# Pop-Up_5_2.net
KiCad netlist of a schematic drawn in EAGLE
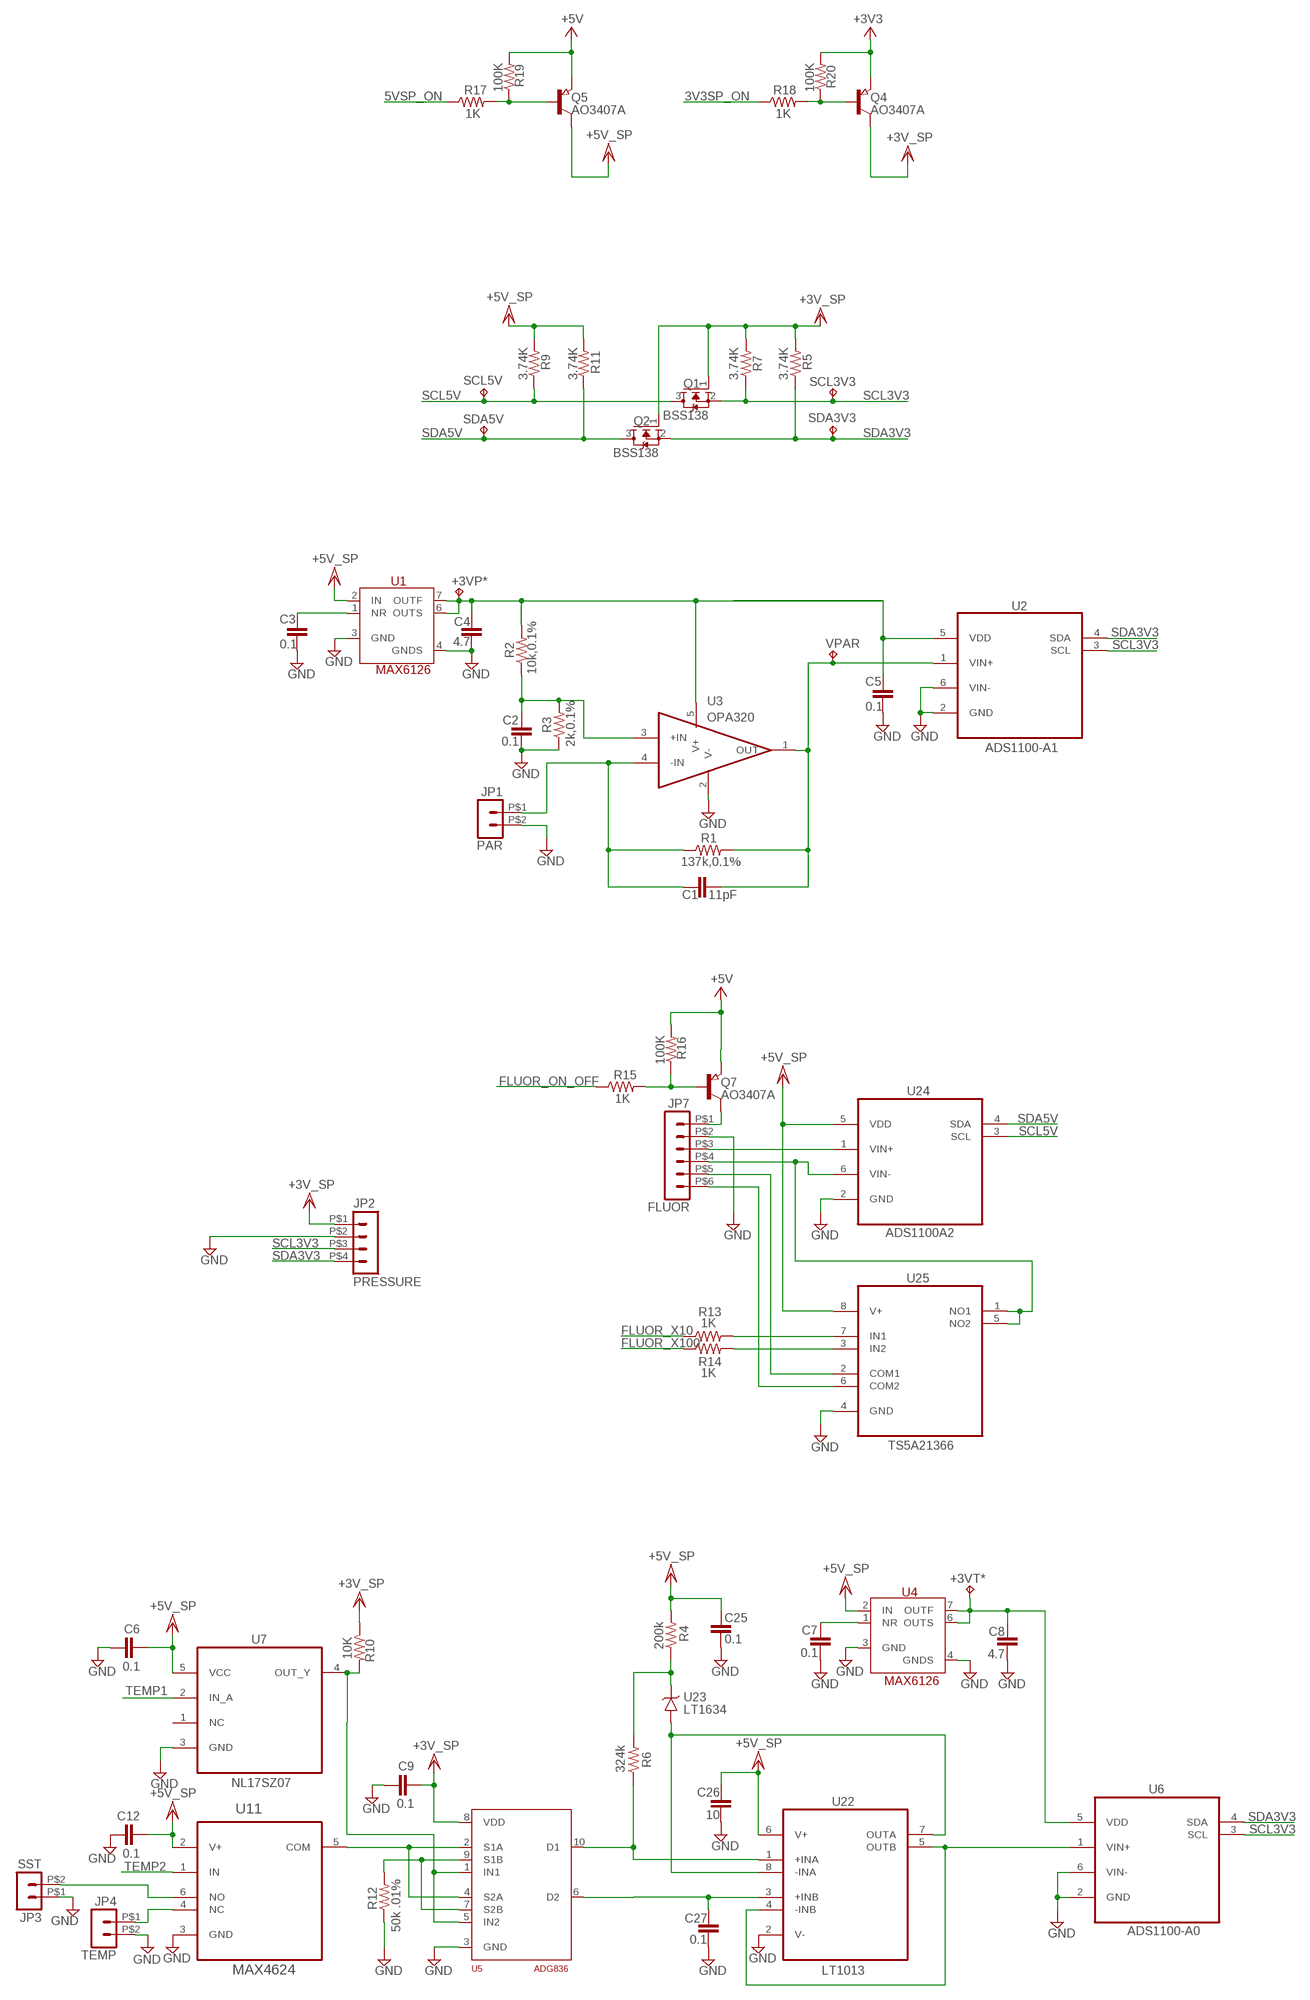
[diagram p0: schematic, sheet 1, part 1 of 2]
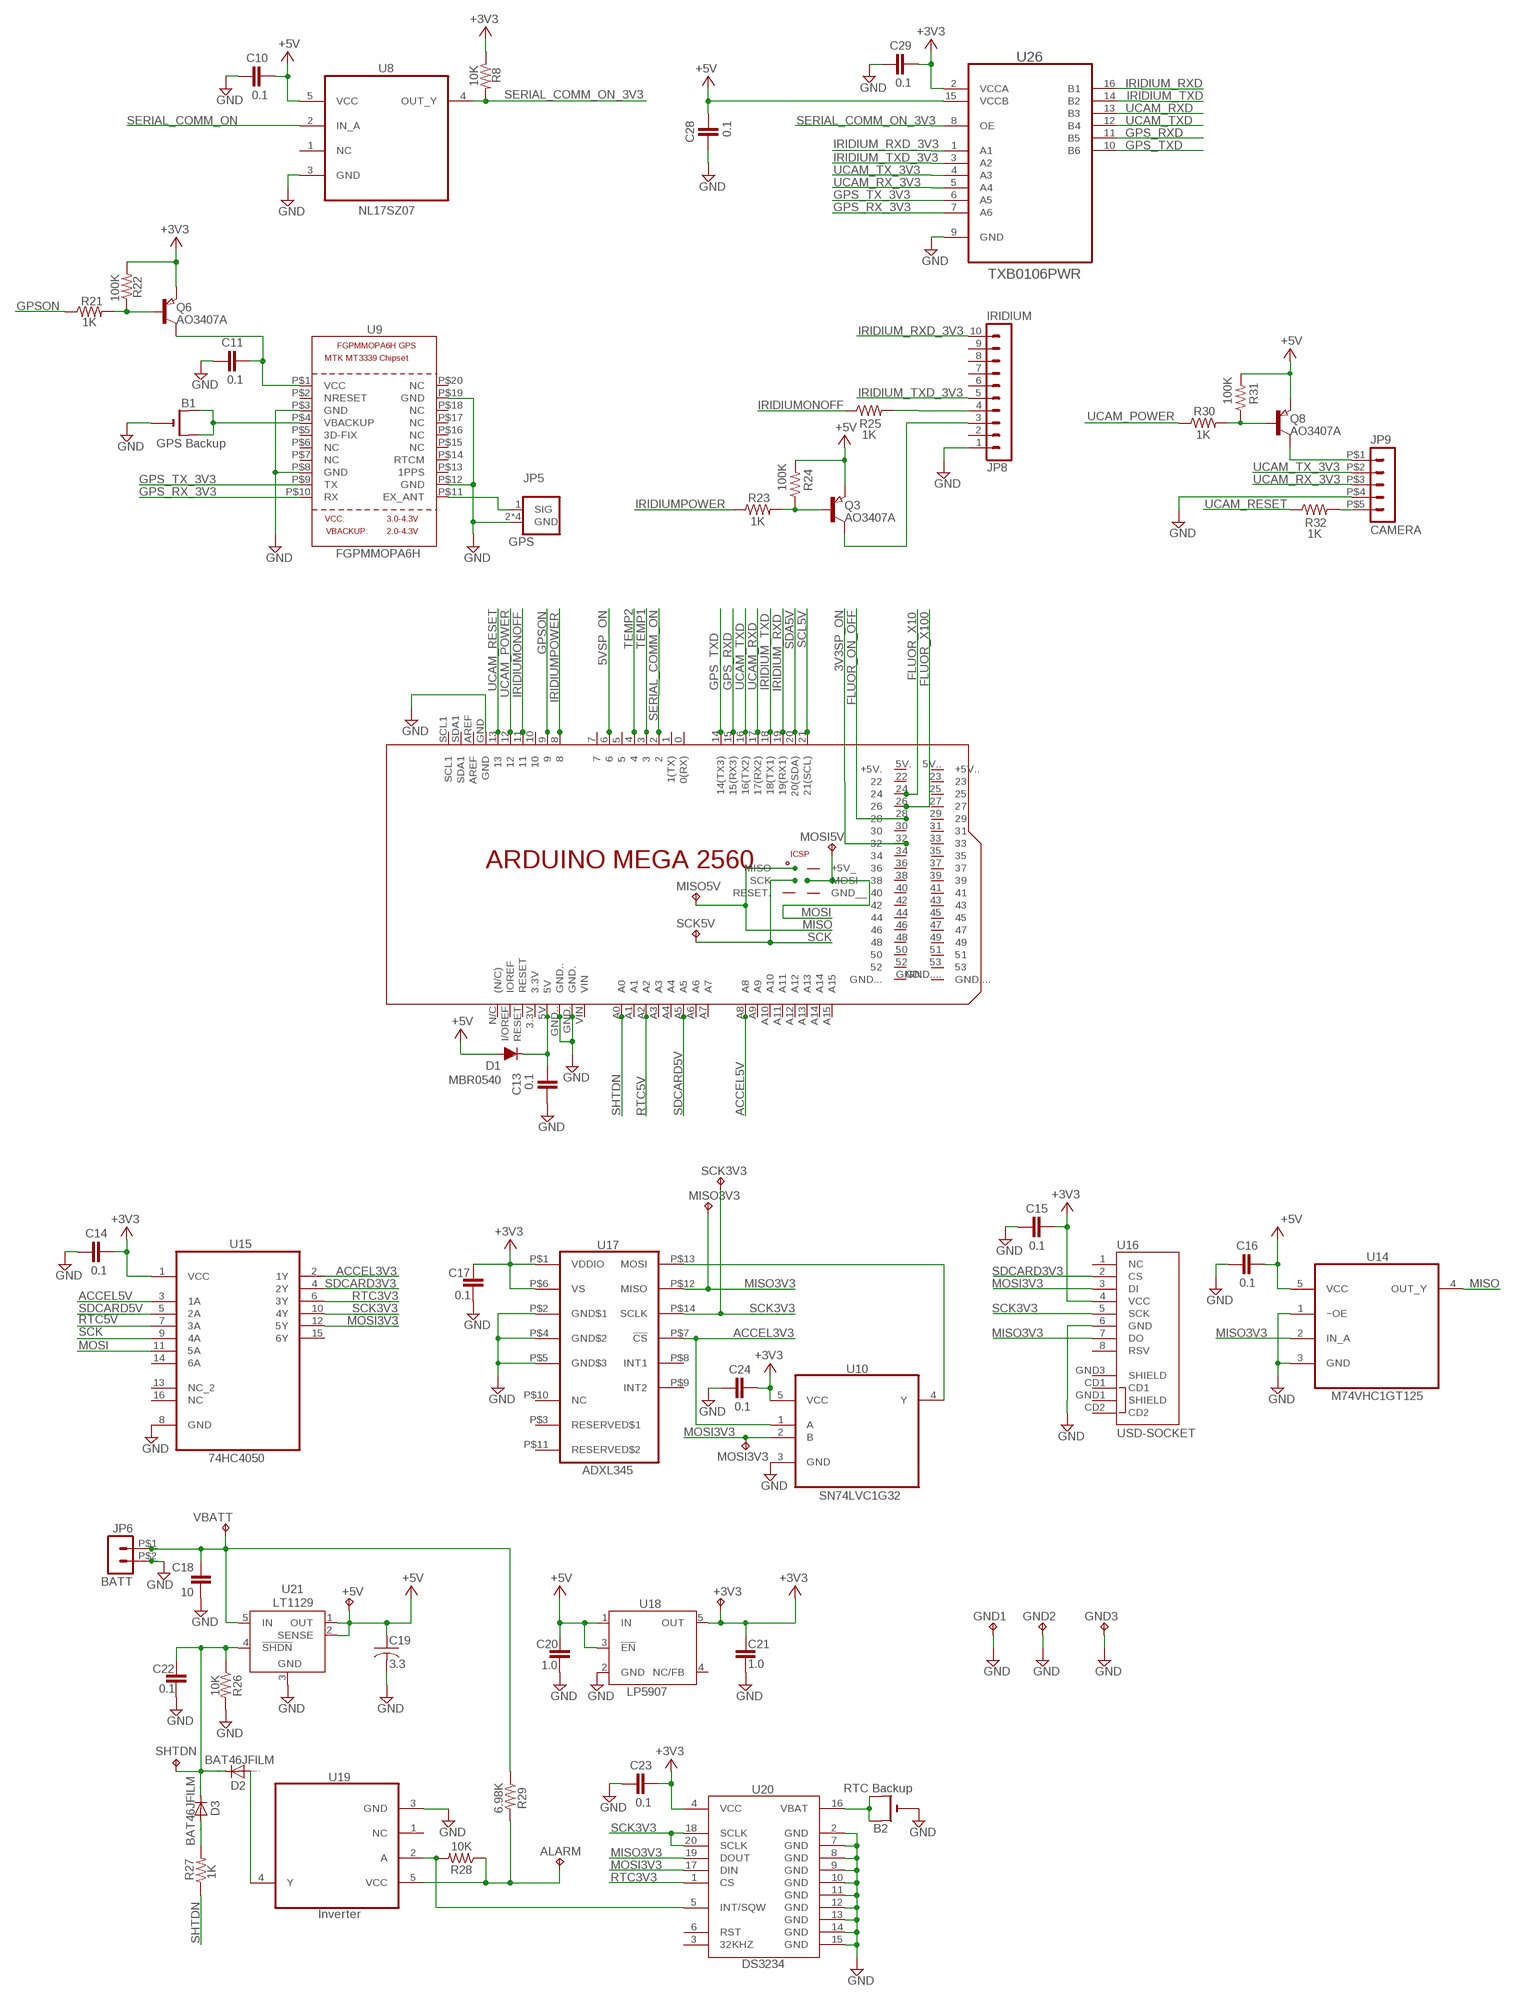
[diagram p1: schematic, sheet 1, part 2 of 2]

(export (version "E")
  (design (tool "Eeschema 10.0.6"))
  (components
    (comp (ref "+3V3")
      (value "TP-040")
      (footprint "eagle-import:TP-040")
      (libsource (lib "eagle-import") (part "TP-040"))
    )
    (comp (ref "+3VP*")
      (value "TP-040")
      (footprint "eagle-import:TP-040")
      (libsource (lib "eagle-import") (part "TP-040"))
    )
    (comp (ref "+3VT*")
      (value "TP-040")
      (footprint "eagle-import:TP-040")
      (libsource (lib "eagle-import") (part "TP-040"))
    )
    (comp (ref "+5V")
      (value "TP-040")
      (footprint "eagle-import:TP-040")
      (libsource (lib "eagle-import") (part "TP-040"))
    )
    (comp (ref "ALARM")
      (value "TP-040")
      (footprint "eagle-import:TP-040")
      (libsource (lib "eagle-import") (part "TP-040"))
    )
    (comp (ref "B1")
      (value "GPS Backup")
      (footprint "eagle-import:CR1220-SMD")
      (libsource (lib "eagle-import") (part "CR1220SMT"))
    )
    (comp (ref "B2")
      (value "RTC Backup")
      (footprint "eagle-import:CR1220-SMD")
      (libsource (lib "eagle-import") (part "CR1220SMT"))
    )
    (comp (ref "C1")
      (value "11pF")
      (footprint "eagle-import:0603-CAP")
      (fields (field (name "MPN") "2222 370 21104"))
      (libsource (lib "eagle-import") (part "CAP0603-CAP"))
    )
    (comp (ref "C2")
      (value "0.1")
      (footprint "eagle-import:0603-CAP")
      (fields (field (name "MPN") "2222 370 21104"))
      (libsource (lib "eagle-import") (part "CAP0603-CAP"))
    )
    (comp (ref "C3")
      (value "0.1")
      (footprint "eagle-import:0603-CAP")
      (fields (field (name "MPN") "2222 370 21104"))
      (libsource (lib "eagle-import") (part "CAP0603-CAP"))
    )
    (comp (ref "C4")
      (value "4.7")
      (footprint "eagle-import:0603-CAP")
      (fields (field (name "MPN") "2222 370 21104"))
      (libsource (lib "eagle-import") (part "CAP0603-CAP"))
    )
    (comp (ref "C5")
      (value "0.1")
      (footprint "eagle-import:0603-CAP")
      (fields (field (name "MPN") "2222 370 21104"))
      (libsource (lib "eagle-import") (part "CAP0603-CAP"))
    )
    (comp (ref "C6")
      (value "0.1")
      (footprint "eagle-import:0603-CAP")
      (fields (field (name "MPN") "2222 370 21104"))
      (libsource (lib "eagle-import") (part "CAP0603-CAP"))
    )
    (comp (ref "C7")
      (value "0.1")
      (footprint "eagle-import:0603-CAP")
      (fields (field (name "MPN") "2222 370 21104"))
      (libsource (lib "eagle-import") (part "CAP0603-CAP"))
    )
    (comp (ref "C8")
      (value "4.7")
      (footprint "eagle-import:0603-CAP")
      (fields (field (name "MPN") "2222 370 21104"))
      (libsource (lib "eagle-import") (part "CAP0603-CAP"))
    )
    (comp (ref "C9")
      (value "0.1")
      (footprint "eagle-import:0603-CAP")
      (fields (field (name "MPN") "2222 370 21104"))
      (libsource (lib "eagle-import") (part "CAP0603-CAP"))
    )
    (comp (ref "C10")
      (value "0.1")
      (footprint "eagle-import:0603-CAP")
      (fields (field (name "MPN") "2222 370 21104"))
      (libsource (lib "eagle-import") (part "CAP0603-CAP"))
    )
    (comp (ref "C11")
      (value "0.1")
      (footprint "eagle-import:0603-CAP")
      (fields (field (name "MPN") "2222 370 21104"))
      (libsource (lib "eagle-import") (part "CAP0603-CAP"))
    )
    (comp (ref "C12")
      (value "0.1")
      (footprint "eagle-import:0603-CAP")
      (fields (field (name "MPN") "2222 370 21104"))
      (libsource (lib "eagle-import") (part "CAP0603-CAP"))
    )
    (comp (ref "C13")
      (value "0.1")
      (footprint "eagle-import:0603-CAP")
      (fields (field (name "MPN") "2222 370 21104"))
      (libsource (lib "eagle-import") (part "CAP0603-CAP"))
    )
    (comp (ref "C14")
      (value "0.1")
      (footprint "eagle-import:0603-CAP")
      (fields (field (name "MPN") "2222 370 21104"))
      (libsource (lib "eagle-import") (part "CAP0603-CAP"))
    )
    (comp (ref "C15")
      (value "0.1")
      (footprint "eagle-import:0603-CAP")
      (fields (field (name "MPN") "2222 370 21104"))
      (libsource (lib "eagle-import") (part "CAP0603-CAP"))
    )
    (comp (ref "C16")
      (value "0.1")
      (footprint "eagle-import:0603-CAP")
      (fields (field (name "MPN") "2222 370 21104"))
      (libsource (lib "eagle-import") (part "CAP0603-CAP"))
    )
    (comp (ref "C17")
      (value "0.1")
      (footprint "eagle-import:0603-CAP")
      (fields (field (name "MPN") "2222 370 21104"))
      (libsource (lib "eagle-import") (part "CAP0603-CAP"))
    )
    (comp (ref "C18")
      (value "10")
      (footprint "eagle-import:C1206")
      (libsource (lib "eagle-import") (part "C-EUC1206"))
    )
    (comp (ref "C19")
      (value "3.3")
      (footprint "eagle-import:C1206")
      (libsource (lib "eagle-import") (part "C-USC1206"))
    )
    (comp (ref "C20")
      (value "1.0")
      (footprint "eagle-import:0603-CAP")
      (fields (field (name "MPN") "2222 370 21104"))
      (libsource (lib "eagle-import") (part "CAP0603-CAP"))
    )
    (comp (ref "C21")
      (value "1.0")
      (footprint "eagle-import:0603-CAP")
      (fields (field (name "MPN") "2222 370 21104"))
      (libsource (lib "eagle-import") (part "CAP0603-CAP"))
    )
    (comp (ref "C22")
      (value "0.1")
      (footprint "eagle-import:0603-CAP")
      (fields (field (name "MPN") "2222 370 21104"))
      (libsource (lib "eagle-import") (part "CAP0603-CAP"))
    )
    (comp (ref "C23")
      (value "0.1")
      (footprint "eagle-import:0603-CAP")
      (fields (field (name "MPN") "2222 370 21104"))
      (libsource (lib "eagle-import") (part "CAP0603-CAP"))
    )
    (comp (ref "C24")
      (value "0.1")
      (footprint "eagle-import:0603-CAP")
      (fields (field (name "MPN") "2222 370 21104"))
      (libsource (lib "eagle-import") (part "CAP0603-CAP"))
    )
    (comp (ref "C25")
      (value "0.1")
      (footprint "eagle-import:0603-CAP")
      (fields (field (name "MPN") "2222 370 21104"))
      (libsource (lib "eagle-import") (part "CAP0603-CAP"))
    )
    (comp (ref "C26")
      (value "10")
      (footprint "eagle-import:C1206")
      (fields (field (name "MPN") "2222 370 21104"))
      (libsource (lib "eagle-import") (part "C-EUC1206"))
    )
    (comp (ref "C27")
      (value "0.1")
      (footprint "eagle-import:0603-CAP")
      (fields (field (name "MPN") "2222 370 21104"))
      (libsource (lib "eagle-import") (part "CAP0603-CAP"))
    )
    (comp (ref "C28")
      (value "0.1")
      (footprint "eagle-import:0603-CAP")
      (fields (field (name "MPN") "2222 370 21104"))
      (libsource (lib "eagle-import") (part "CAP0603-CAP"))
    )
    (comp (ref "C29")
      (value "0.1")
      (footprint "eagle-import:0603-CAP")
      (fields (field (name "MPN") "2222 370 21104"))
      (libsource (lib "eagle-import") (part "CAP0603-CAP"))
    )
    (comp (ref "D1")
      (value "MBR0540")
      (footprint "eagle-import:SOD123")
      (libsource (lib "eagle-import") (part "D-FILL-SOD123"))
    )
    (comp (ref "D2")
      (value "BAT46JFILM")
      (footprint "eagle-import:SOD323-R")
      (libsource (lib "eagle-import") (part "DIODE-SOD323-R"))
    )
    (comp (ref "D3")
      (value "BAT46JFILM")
      (footprint "eagle-import:SOD323-R")
      (libsource (lib "eagle-import") (part "DIODE-SOD323-R"))
    )
    (comp (ref "GND1")
      (value "TP-040")
      (footprint "eagle-import:TP-040")
      (libsource (lib "eagle-import") (part "TP-040"))
    )
    (comp (ref "GND2")
      (value "TP-040")
      (footprint "eagle-import:TP-040")
      (libsource (lib "eagle-import") (part "TP-040"))
    )
    (comp (ref "GND3")
      (value "TP-040")
      (footprint "eagle-import:TP-040")
      (libsource (lib "eagle-import") (part "TP-040"))
    )
    (comp (ref "JP1")
      (value "PAR")
      (footprint "eagle-import:43650-0215")
      (libsource (lib "eagle-import") (part "HEADER_POS2_?43650-0215"))
    )
    (comp (ref "JP2")
      (value "PRESSURE")
      (footprint "eagle-import:43650-0415")
      (libsource (lib "eagle-import") (part "HEADER_POS4_?43650-0415"))
    )
    (comp (ref "JP3")
      (value "SST")
      (footprint "eagle-import:43650-0215")
      (libsource (lib "eagle-import") (part "HEADER_POS2_?43650-0215"))
    )
    (comp (ref "JP4")
      (value "TEMP")
      (footprint "eagle-import:43650-0215")
      (libsource (lib "eagle-import") (part "HEADER_POS2_?43650-0215"))
    )
    (comp (ref "JP5")
      (value "GPS")
      (footprint "eagle-import:AMPHENOL_901-9895-RFX")
      (fields (field (name "MPN") "901-9895-RFX"))
      (libsource (lib "eagle-import") (part "901-9895-RFX"))
    )
    (comp (ref "JP6")
      (value "BATT")
      (footprint "eagle-import:43650-0215")
      (libsource (lib "eagle-import") (part "HEADER_POS2_?43650-0215"))
    )
    (comp (ref "JP7")
      (value "FLUOR")
      (footprint "eagle-import:43045-0612")
      (libsource (lib "eagle-import") (part "HEADER_POS6_?43045-0612"))
    )
    (comp (ref "JP8")
      (value "IRIDIUM")
      (footprint "eagle-import:53398-1010")
      (libsource (lib "eagle-import") (part "53398-1010"))
    )
    (comp (ref "JP9")
      (value "CAMERA")
      (footprint "eagle-import:43650-0515")
      (libsource (lib "eagle-import") (part "HEADER_POS5_?43650-0515"))
    )
    (comp (ref "MISO3V3")
      (value "TP-040")
      (footprint "eagle-import:TP-040")
      (libsource (lib "eagle-import") (part "TP-040"))
    )
    (comp (ref "MISO5V")
      (value "TP-040")
      (footprint "eagle-import:TP-040")
      (libsource (lib "eagle-import") (part "TP-040"))
    )
    (comp (ref "MOSI3V3")
      (value "TP-040")
      (footprint "eagle-import:TP-040")
      (libsource (lib "eagle-import") (part "TP-040"))
    )
    (comp (ref "MOSI5V")
      (value "TP-040")
      (footprint "eagle-import:TP-040")
      (libsource (lib "eagle-import") (part "TP-040"))
    )
    (comp (ref "Q1")
      (value "BSS138")
      (footprint "eagle-import:SOT23")
      (libsource (lib "eagle-import") (part "MOSFET-NREFLOW"))
    )
    (comp (ref "Q2")
      (value "BSS138")
      (footprint "eagle-import:SOT23")
      (libsource (lib "eagle-import") (part "MOSFET-NREFLOW"))
    )
    (comp (ref "Q3")
      (value "AO3407A")
      (footprint "eagle-import:SOT23")
      (libsource (lib "eagle-import") (part "PNP-TRANSISTOR_SOT23"))
    )
    (comp (ref "Q4")
      (value "AO3407A")
      (footprint "eagle-import:SOT23")
      (libsource (lib "eagle-import") (part "PNP-TRANSISTOR_SOT23"))
    )
    (comp (ref "Q5")
      (value "AO3407A")
      (footprint "eagle-import:SOT23")
      (libsource (lib "eagle-import") (part "PNP-TRANSISTOR_SOT23"))
    )
    (comp (ref "Q6")
      (value "AO3407A")
      (footprint "eagle-import:SOT23")
      (libsource (lib "eagle-import") (part "PNP-TRANSISTOR_SOT23"))
    )
    (comp (ref "Q7")
      (value "AO3407A")
      (footprint "eagle-import:SOT23")
      (libsource (lib "eagle-import") (part "PNP-TRANSISTOR_SOT23"))
    )
    (comp (ref "Q8")
      (value "AO3407A")
      (footprint "eagle-import:SOT23")
      (libsource (lib "eagle-import") (part "PNP-TRANSISTOR_SOT23"))
    )
    (comp (ref "R1")
      (value "137k,0.1%")
      (footprint "eagle-import:R0603")
      (libsource (lib "eagle-import") (part "R-US_R0603"))
    )
    (comp (ref "R2")
      (value "10k,0.1%")
      (footprint "eagle-import:R0603")
      (libsource (lib "eagle-import") (part "R-US_R0603"))
    )
    (comp (ref "R3")
      (value "2k,0.1%")
      (footprint "eagle-import:R0603")
      (libsource (lib "eagle-import") (part "R-US_R0603"))
    )
    (comp (ref "R4")
      (value "200k")
      (footprint "eagle-import:R1206")
      (libsource (lib "eagle-import") (part "R-US_R1206"))
    )
    (comp (ref "R5")
      (value "3.74K")
      (footprint "eagle-import:R0603")
      (libsource (lib "eagle-import") (part "R-US_R0603"))
    )
    (comp (ref "R6")
      (value "324k")
      (footprint "eagle-import:R1206")
      (libsource (lib "eagle-import") (part "R-US_R1206"))
    )
    (comp (ref "R7")
      (value "3.74K")
      (footprint "eagle-import:R0603")
      (libsource (lib "eagle-import") (part "R-US_R0603"))
    )
    (comp (ref "R8")
      (value "10K")
      (footprint "eagle-import:R0603")
      (libsource (lib "eagle-import") (part "R-US_R0603"))
    )
    (comp (ref "R9")
      (value "3.74K")
      (footprint "eagle-import:R0603")
      (libsource (lib "eagle-import") (part "R-US_R0603"))
    )
    (comp (ref "R10")
      (value "10K")
      (footprint "eagle-import:R0603")
      (libsource (lib "eagle-import") (part "R-US_R0603"))
    )
    (comp (ref "R11")
      (value "3.74K")
      (footprint "eagle-import:R0603")
      (libsource (lib "eagle-import") (part "R-US_R0603"))
    )
    (comp (ref "R12")
      (value "50k .01%")
      (footprint "eagle-import:R2010")
      (libsource (lib "eagle-import") (part "R-US_R2010"))
    )
    (comp (ref "R13")
      (value "1K")
      (footprint "eagle-import:R0603")
      (libsource (lib "eagle-import") (part "R-US_R0603"))
    )
    (comp (ref "R14")
      (value "1K")
      (footprint "eagle-import:R0603")
      (libsource (lib "eagle-import") (part "R-US_R0603"))
    )
    (comp (ref "R15")
      (value "1K")
      (footprint "eagle-import:R0603")
      (libsource (lib "eagle-import") (part "R-US_R0603"))
    )
    (comp (ref "R16")
      (value "100K")
      (footprint "eagle-import:R0603")
      (libsource (lib "eagle-import") (part "R-US_R0603"))
    )
    (comp (ref "R17")
      (value "1K")
      (footprint "eagle-import:R0603")
      (libsource (lib "eagle-import") (part "R-US_R0603"))
    )
    (comp (ref "R18")
      (value "1K")
      (footprint "eagle-import:R0603")
      (libsource (lib "eagle-import") (part "R-US_R0603"))
    )
    (comp (ref "R19")
      (value "100K")
      (footprint "eagle-import:R0603")
      (libsource (lib "eagle-import") (part "R-US_R0603"))
    )
    (comp (ref "R20")
      (value "100K")
      (footprint "eagle-import:R0603")
      (libsource (lib "eagle-import") (part "R-US_R0603"))
    )
    (comp (ref "R21")
      (value "1K")
      (footprint "eagle-import:R0603")
      (libsource (lib "eagle-import") (part "R-US_R0603"))
    )
    (comp (ref "R22")
      (value "100K")
      (footprint "eagle-import:R0603")
      (libsource (lib "eagle-import") (part "R-US_R0603"))
    )
    (comp (ref "R23")
      (value "1K")
      (footprint "eagle-import:R0603")
      (libsource (lib "eagle-import") (part "R-US_R0603"))
    )
    (comp (ref "R24")
      (value "100K")
      (footprint "eagle-import:R0603")
      (libsource (lib "eagle-import") (part "R-US_R0603"))
    )
    (comp (ref "R25")
      (value "1K")
      (footprint "eagle-import:R0603")
      (libsource (lib "eagle-import") (part "R-US_R0603"))
    )
    (comp (ref "R26")
      (value "10K")
      (footprint "eagle-import:R0603")
      (libsource (lib "eagle-import") (part "R-US_R0603"))
    )
    (comp (ref "R27")
      (value "1K")
      (footprint "eagle-import:R0603")
      (libsource (lib "eagle-import") (part "R-US_R0603"))
    )
    (comp (ref "R28")
      (value "10K")
      (footprint "eagle-import:R0603")
      (libsource (lib "eagle-import") (part "R-US_R0603"))
    )
    (comp (ref "R29")
      (value "6.98K")
      (footprint "eagle-import:R0603")
      (libsource (lib "eagle-import") (part "R-US_R0603"))
    )
    (comp (ref "R30")
      (value "1K")
      (footprint "eagle-import:R0603")
      (libsource (lib "eagle-import") (part "R-US_R0603"))
    )
    (comp (ref "R31")
      (value "100K")
      (footprint "eagle-import:R0603")
      (libsource (lib "eagle-import") (part "R-US_R0603"))
    )
    (comp (ref "R32")
      (value "1K")
      (footprint "eagle-import:R0603")
      (libsource (lib "eagle-import") (part "R-US_R0603"))
    )
    (comp (ref "SCK3V3")
      (value "TP-040")
      (footprint "eagle-import:TP-040")
      (libsource (lib "eagle-import") (part "TP-040"))
    )
    (comp (ref "SCK5V")
      (value "TP-040")
      (footprint "eagle-import:TP-040")
      (libsource (lib "eagle-import") (part "TP-040"))
    )
    (comp (ref "SCL3V3")
      (value "TP-040")
      (footprint "eagle-import:TP-040")
      (libsource (lib "eagle-import") (part "TP-040"))
    )
    (comp (ref "SCL5V")
      (value "TP-040")
      (footprint "eagle-import:TP-040")
      (libsource (lib "eagle-import") (part "TP-040"))
    )
    (comp (ref "SDA3V3")
      (value "TP-040")
      (footprint "eagle-import:TP-040")
      (libsource (lib "eagle-import") (part "TP-040"))
    )
    (comp (ref "SDA5V")
      (value "TP-040")
      (footprint "eagle-import:TP-040")
      (libsource (lib "eagle-import") (part "TP-040"))
    )
    (comp (ref "SHTDN")
      (value "TP-040")
      (footprint "eagle-import:TP-040")
      (libsource (lib "eagle-import") (part "TP-040"))
    )
    (comp (ref "U1")
      (value "MAX6126")
      (footprint "eagle-import:SOIC127P600X175-8N")
      (libsource (lib "eagle-import") (part "MAX6126"))
    )
    (comp (ref "U2")
      (value "ADS1100-A1")
      (footprint "eagle-import:SOT95P280X145-6N")
      (fields (field (name "MPN") "ADS1100A0IDBVT"))
      (libsource (lib "eagle-import") (part "ADS1100A0IDBVT"))
    )
    (comp (ref "U3")
      (value "OPA320")
      (footprint "eagle-import:SOT95P280X145-5N")
      (fields (field (name "MPN") "OPA320AIDBVT"))
      (libsource (lib "eagle-import") (part "OPA320AIDBVT"))
    )
    (comp (ref "U4")
      (value "MAX6126")
      (footprint "eagle-import:SOIC127P600X175-8N")
      (libsource (lib "eagle-import") (part "MAX6126"))
    )
    (comp (ref "U5")
      (value "ADG836")
      (footprint "eagle-import:MSOP10")
      (libsource (lib "eagle-import") (part "ADG836"))
    )
    (comp (ref "U6")
      (value "ADS1100-A0")
      (footprint "eagle-import:SOT95P280X145-6N")
      (fields (field (name "MPN") "ADS1100A0IDBVT"))
      (libsource (lib "eagle-import") (part "ADS1100A0IDBVT"))
    )
    (comp (ref "U7")
      (value "NL17SZ07")
      (footprint "eagle-import:SOT65P210X110-5N")
      (fields (field (name "MPN") "NL17SZ07DFT2G"))
      (libsource (lib "eagle-import") (part "NL17SZ07DFT2G"))
    )
    (comp (ref "U8")
      (value "NL17SZ07")
      (footprint "eagle-import:SOT65P210X110-5N")
      (fields (field (name "MPN") "NL17SZ07DFT2G"))
      (libsource (lib "eagle-import") (part "NL17SZ07DFT2G"))
    )
    (comp (ref "U9")
      (value "FGPMMOPA6H")
      (footprint "eagle-import:FGPMMOPA6H")
      (libsource (lib "eagle-import") (part "GPS_FGPMMOPA6H"))
    )
    (comp (ref "U10")
      (value "SN74LVC1G32")
      (footprint "eagle-import:SOT65P210X110-5N")
      (fields (field (name "MPN") "SN74LVC1G32DCKT"))
      (libsource (lib "eagle-import") (part "SN74LVC1G32DCKT"))
    )
    (comp (ref "U11")
      (value "MAX4624")
      (footprint "eagle-import:SOT95P275X100-6N")
      (fields (field (name "MPN") "MAX4624EZT+T"))
      (libsource (lib "eagle-import") (part "MAX4624EZT+T"))
    )
    (comp (ref "U12")
      (value "Arduino MEGA2650")
      (footprint "eagle-import:MEGA2650_UPSIDEDOWNMOUNT")
      (libsource (lib "eagle-import") (part "MEGA2650_UPSIDEDOWNMOUNT"))
    )
    (comp (ref "U14")
      (value "M74VHC1GT125")
      (footprint "eagle-import:SOT65P210X110-5N")
      (fields (field (name "MPN") "M74VHC1GT125DF1G"))
      (libsource (lib "eagle-import") (part "M74VHC1GT125DF1G"))
    )
    (comp (ref "U15")
      (value "74HC4050")
      (footprint "eagle-import:SOIC127P600X175-16N")
      (fields (field (name "MPN") "M74HC4050RM13TR"))
      (libsource (lib "eagle-import") (part "M74HC4050RM13TR"))
    )
    (comp (ref "U16")
      (value "USD-SOCKET")
      (footprint "eagle-import:MICROSD_1_1")
      (libsource (lib "eagle-import") (part "USD-SOCKET"))
    )
    (comp (ref "U17")
      (value "ADXL345")
      (footprint "eagle-import:LGA14")
      (libsource (lib "eagle-import") (part "ADXL345"))
    )
    (comp (ref "U18")
      (value "LP5907")
      (footprint "eagle-import:SOT23-DBV")
      (fields (field (name "MF") "TEXAS INSTRUMENTS") (field (name "MPN") "TPS77033DBVT"))
      (libsource (lib "eagle-import") (part "TPS77033"))
    )
    (comp (ref "U19")
      (value "Inverter")
      (footprint "eagle-import:SOT95P280X145-5N")
      (fields (field (name "MPN") "1P1G14MDBVREPG4") (field (name "OC_NEWARK") "unknown"))
      (libsource (lib "eagle-import") (part "1P1G14MDBVREPG4"))
    )
    (comp (ref "U20")
      (value "DS3234")
      (footprint "eagle-import:DS3234")
      (libsource (lib "eagle-import") (part "DS3234"))
    )
    (comp (ref "U21")
      (value "LT1129")
      (footprint "eagle-import:Q5-DD")
      (fields (field (name "MPN") "LT1129CQ-5#PBF"))
      (libsource (lib "eagle-import") (part "LT1129CQ-5"))
    )
    (comp (ref "U22")
      (value "LT1013")
      (footprint "eagle-import:SOIC127P600X175-8N")
      (fields (field (name "MPN") "LT1013IS8#PBF"))
      (libsource (lib "eagle-import") (part "LT1013IS8PBF"))
    )
    (comp (ref "U23")
      (value "LT1634")
      (footprint "eagle-import:S8")
      (libsource (lib "eagle-import") (part "LT1634BIS8-1.25"))
    )
    (comp (ref "U24")
      (value "ADS1100A2")
      (footprint "eagle-import:SOT95P280X145-6N")
      (fields (field (name "MPN") "ADS1100A2IDBVT"))
      (libsource (lib "eagle-import") (part "ADS1100A2IDBVT"))
    )
    (comp (ref "U25")
      (value "TS5A21366")
      (footprint "eagle-import:SOP50P310X90-8N")
      (fields (field (name "MPN") "TS5A21366DCUR"))
      (libsource (lib "eagle-import") (part "TS5A21366DCUR"))
    )
    (comp (ref "U26")
      (value "TXB0106PWR")
      (footprint "eagle-import:SOP65P640X120-16N")
      (libsource (lib "eagle-import") (part "TXB0106PWR"))
    )
    (comp (ref "VBATT")
      (value "TP-040")
      (footprint "eagle-import:TP-040")
      (libsource (lib "eagle-import") (part "TP-040"))
    )
    (comp (ref "VPAR")
      (value "TP-040")
      (footprint "eagle-import:TP-040")
      (libsource (lib "eagle-import") (part "TP-040"))
    )
  )
  (nets
    (net (code "1") (name "+3V3") (class "Default")
      (node (ref "+3V3") (pin "1") (pinfunction "1_1") (pintype "passive"))
      (node (ref "C14") (pin "1") (pinfunction "1_1") (pintype "passive"))
      (node (ref "C15") (pin "1") (pinfunction "1_1") (pintype "passive"))
      (node (ref "C17") (pin "1") (pinfunction "1_1") (pintype "passive"))
      (node (ref "C21") (pin "1") (pinfunction "1_1") (pintype "passive"))
      (node (ref "C23") (pin "1") (pinfunction "1_1") (pintype "passive"))
      (node (ref "C24") (pin "1") (pinfunction "1_1") (pintype "passive"))
      (node (ref "C29") (pin "1") (pinfunction "1_1") (pintype "passive"))
      (node (ref "Q4") (pin "2") (pinfunction "E_2") (pintype "passive"))
      (node (ref "Q6") (pin "2") (pinfunction "E_2") (pintype "passive"))
      (node (ref "R20") (pin "2") (pinfunction "2_2") (pintype "passive"))
      (node (ref "R22") (pin "2") (pinfunction "2_2") (pintype "passive"))
      (node (ref "R8") (pin "1") (pinfunction "1_1") (pintype "passive"))
      (node (ref "U10") (pin "5") (pinfunction "VCC_5") (pintype "power_in"))
      (node (ref "U15") (pin "1") (pinfunction "VCC_1") (pintype "power_in"))
      (node (ref "U16") (pin "4") (pinfunction "VCC_4") (pintype "bidirectional"))
      (node (ref "U17") (pin "P$1") (pinfunction "VDDIO_P$1") (pintype "power_in"))
      (node (ref "U17") (pin "P$6") (pinfunction "VS_P$6") (pintype "power_in"))
      (node (ref "U18") (pin "5") (pinfunction "OUT_5") (pintype "passive"))
      (node (ref "U20") (pin "4") (pinfunction "VCC_4") (pintype "bidirectional"))
      (node (ref "U26") (pin "2") (pinfunction "VCCA_2") (pintype "power_in"))
    )
    (net (code "2") (name "+3V_SP") (class "Default")
      (node (ref "C9") (pin "1") (pinfunction "1_1") (pintype "passive"))
      (node (ref "JP2") (pin "P$1") (pinfunction "1_P$1") (pintype "passive"))
      (node (ref "Q1") (pin "1") (pinfunction "G_1") (pintype "bidirectional"))
      (node (ref "Q2") (pin "1") (pinfunction "G_1") (pintype "bidirectional"))
      (node (ref "Q4") (pin "3") (pinfunction "C_3") (pintype "passive"))
      (node (ref "R10") (pin "1") (pinfunction "1_1") (pintype "passive"))
      (node (ref "R5") (pin "2") (pinfunction "2_2") (pintype "passive"))
      (node (ref "R7") (pin "2") (pinfunction "2_2") (pintype "passive"))
      (node (ref "U5") (pin "8") (pinfunction "VDD_8") (pintype "bidirectional"))
    )
    (net (code "3") (name "+5V") (class "Default")
      (node (ref "+5V") (pin "1") (pinfunction "1_1") (pintype "passive"))
      (node (ref "C10") (pin "1") (pinfunction "1_1") (pintype "passive"))
      (node (ref "C16") (pin "1") (pinfunction "1_1") (pintype "passive"))
      (node (ref "C19") (pin "1") (pinfunction "1_1") (pintype "passive"))
      (node (ref "C20") (pin "1") (pinfunction "1_1") (pintype "passive"))
      (node (ref "C28") (pin "1") (pinfunction "1_1") (pintype "passive"))
      (node (ref "D1") (pin "2") (pinfunction "A_2") (pintype "passive"))
      (node (ref "Q3") (pin "2") (pinfunction "E_2") (pintype "passive"))
      (node (ref "Q5") (pin "2") (pinfunction "E_2") (pintype "passive"))
      (node (ref "Q7") (pin "2") (pinfunction "E_2") (pintype "passive"))
      (node (ref "Q8") (pin "2") (pinfunction "E_2") (pintype "passive"))
      (node (ref "R16") (pin "2") (pinfunction "2_2") (pintype "passive"))
      (node (ref "R19") (pin "2") (pinfunction "2_2") (pintype "passive"))
      (node (ref "R24") (pin "2") (pinfunction "2_2") (pintype "passive"))
      (node (ref "R31") (pin "2") (pinfunction "2_2") (pintype "passive"))
      (node (ref "U14") (pin "5") (pinfunction "VCC_5") (pintype "power_in"))
      (node (ref "U18") (pin "1") (pinfunction "IN_1") (pintype "input"))
      (node (ref "U18") (pin "3") (pinfunction "~{EN}_3") (pintype "input"))
      (node (ref "U21") (pin "1") (pinfunction "OUT_1") (pintype "output"))
      (node (ref "U21") (pin "2") (pinfunction "SENSE_2") (pintype "input"))
      (node (ref "U26") (pin "15") (pinfunction "VCCB_15") (pintype "power_in"))
      (node (ref "U8") (pin "5") (pinfunction "VCC_5") (pintype "power_in"))
    )
    (net (code "4") (name "+5V_SP") (class "Default")
      (node (ref "C12") (pin "1") (pinfunction "1_1") (pintype "passive"))
      (node (ref "C25") (pin "1") (pinfunction "1_1") (pintype "passive"))
      (node (ref "C26") (pin "1") (pinfunction "1_1") (pintype "passive"))
      (node (ref "C6") (pin "1") (pinfunction "1_1") (pintype "passive"))
      (node (ref "Q5") (pin "3") (pinfunction "C_3") (pintype "passive"))
      (node (ref "R11") (pin "2") (pinfunction "2_2") (pintype "passive"))
      (node (ref "R4") (pin "2") (pinfunction "2_2") (pintype "passive"))
      (node (ref "R9") (pin "2") (pinfunction "2_2") (pintype "passive"))
      (node (ref "U1") (pin "2") (pinfunction "IN_2") (pintype "input"))
      (node (ref "U11") (pin "2") (pinfunction "V+_2") (pintype "power_in"))
      (node (ref "U22") (pin "6") (pinfunction "V+_6") (pintype "power_in"))
      (node (ref "U24") (pin "5") (pinfunction "VDD_5") (pintype "power_in"))
      (node (ref "U25") (pin "8") (pinfunction "V+_8") (pintype "power_in"))
      (node (ref "U4") (pin "2") (pinfunction "IN_2") (pintype "input"))
      (node (ref "U7") (pin "5") (pinfunction "VCC_5") (pintype "power_in"))
    )
    (net (code "5") (name "/3V3SP_ON") (class "Default")
      (node (ref "R18") (pin "1") (pinfunction "1_1") (pintype "passive"))
      (node (ref "U12") (pin "32") (pinfunction "32_32") (pintype "bidirectional"))
    )
    (net (code "6") (name "/5VSP_ON") (class "Default")
      (node (ref "R17") (pin "1") (pinfunction "1_1") (pintype "passive"))
      (node (ref "U12") (pin "6") (pinfunction "6_6") (pintype "bidirectional"))
    )
    (net (code "7") (name "/ACCEL3V3") (class "Default")
      (node (ref "U10") (pin "1") (pinfunction "A_1") (pintype "input"))
      (node (ref "U15") (pin "2") (pinfunction "1Y_2") (pintype "output"))
      (node (ref "U17") (pin "P$7") (pinfunction "~{CS}_P$7") (pintype "input"))
    )
    (net (code "8") (name "/ACCEL5V") (class "Default")
      (node (ref "U12") (pin "A8") (pinfunction "A8_A8") (pintype "bidirectional"))
      (node (ref "U15") (pin "3") (pinfunction "1A_3") (pintype "input"))
    )
    (net (code "9") (name "/FLUOR_ON_OFF") (class "Default")
      (node (ref "R15") (pin "1") (pinfunction "1_1") (pintype "passive"))
      (node (ref "U12") (pin "28") (pinfunction "28_28") (pintype "bidirectional"))
    )
    (net (code "10") (name "/FLUOR_X10") (class "Default")
      (node (ref "R13") (pin "1") (pinfunction "1_1") (pintype "passive"))
      (node (ref "U12") (pin "24") (pinfunction "24_24") (pintype "bidirectional"))
    )
    (net (code "11") (name "/FLUOR_X100") (class "Default")
      (node (ref "R14") (pin "1") (pinfunction "1_1") (pintype "passive"))
      (node (ref "U12") (pin "26") (pinfunction "26_26") (pintype "bidirectional"))
    )
    (net (code "12") (name "/GPSON") (class "Default")
      (node (ref "R21") (pin "1") (pinfunction "1_1") (pintype "passive"))
      (node (ref "U12") (pin "9") (pinfunction "9_9") (pintype "bidirectional"))
    )
    (net (code "13") (name "/GPS_RXD") (class "Default")
      (node (ref "U12") (pin "15") (pinfunction "15(RX3)_15") (pintype "bidirectional"))
      (node (ref "U26") (pin "11") (pinfunction "B5_11") (pintype "bidirectional"))
    )
    (net (code "14") (name "/GPS_RX_3V3") (class "Default")
      (node (ref "U26") (pin "7") (pinfunction "A6_7") (pintype "bidirectional"))
      (node (ref "U9") (pin "P$10") (pinfunction "RX_P$10") (pintype "bidirectional"))
    )
    (net (code "15") (name "/GPS_TXD") (class "Default")
      (node (ref "U12") (pin "14") (pinfunction "14(TX3)_14") (pintype "bidirectional"))
      (node (ref "U26") (pin "10") (pinfunction "B6_10") (pintype "bidirectional"))
    )
    (net (code "16") (name "/GPS_TX_3V3") (class "Default")
      (node (ref "U26") (pin "6") (pinfunction "A5_6") (pintype "bidirectional"))
      (node (ref "U9") (pin "P$9") (pinfunction "TX_P$9") (pintype "bidirectional"))
    )
    (net (code "17") (name "/IRIDIUMONOFF") (class "Default")
      (node (ref "R25") (pin "1") (pinfunction "1_1") (pintype "passive"))
      (node (ref "U12") (pin "11") (pinfunction "11_11") (pintype "bidirectional"))
    )
    (net (code "18") (name "/IRIDIUMPOWER") (class "Default")
      (node (ref "R23") (pin "1") (pinfunction "1_1") (pintype "passive"))
      (node (ref "U12") (pin "8") (pinfunction "8_8") (pintype "bidirectional"))
    )
    (net (code "19") (name "/IRIDIUM_RXD") (class "Default")
      (node (ref "U12") (pin "19") (pinfunction "19(RX1)_19") (pintype "bidirectional"))
      (node (ref "U26") (pin "16") (pinfunction "B1_16") (pintype "bidirectional"))
    )
    (net (code "20") (name "/IRIDIUM_RXD_3V3") (class "Default")
      (node (ref "JP8") (pin "10") (pinfunction "10_10") (pintype "passive"))
      (node (ref "U26") (pin "1") (pinfunction "A1_1") (pintype "bidirectional"))
    )
    (net (code "21") (name "/IRIDIUM_TXD") (class "Default")
      (node (ref "U12") (pin "18") (pinfunction "18(TX1)_18") (pintype "bidirectional"))
      (node (ref "U26") (pin "14") (pinfunction "B2_14") (pintype "bidirectional"))
    )
    (net (code "22") (name "/IRIDIUM_TXD_3V3") (class "Default")
      (node (ref "JP8") (pin "5") (pinfunction "5_5") (pintype "passive"))
      (node (ref "U26") (pin "3") (pinfunction "A2_3") (pintype "bidirectional"))
    )
    (net (code "23") (name "/MISO") (class "Default")
      (node (ref "MISO5V") (pin "1") (pinfunction "1_1") (pintype "passive"))
      (node (ref "U12") (pin "MISO") (pinfunction "MISO_MISO") (pintype "bidirectional"))
      (node (ref "U14") (pin "4") (pinfunction "OUT_Y_4") (pintype "output"))
    )
    (net (code "24") (name "/MISO3V3") (class "Default")
      (node (ref "MISO3V3") (pin "1") (pinfunction "1_1") (pintype "passive"))
      (node (ref "U14") (pin "2") (pinfunction "IN_A_2") (pintype "input"))
      (node (ref "U16") (pin "7") (pinfunction "DO_7") (pintype "bidirectional"))
      (node (ref "U17") (pin "P$12") (pinfunction "MISO_P$12") (pintype "output"))
      (node (ref "U20") (pin "19") (pinfunction "DOUT_19") (pintype "bidirectional"))
    )
    (net (code "25") (name "/MOSI") (class "Default")
      (node (ref "MOSI5V") (pin "1") (pinfunction "1_1") (pintype "passive"))
      (node (ref "U12") (pin "MOSI") (pinfunction "MOSI_MOSI") (pintype "bidirectional"))
      (node (ref "U15") (pin "11") (pinfunction "5A_11") (pintype "input"))
    )
    (net (code "26") (name "/MOSI3V3") (class "Default")
      (node (ref "MOSI3V3") (pin "1") (pinfunction "1_1") (pintype "passive"))
      (node (ref "U10") (pin "2") (pinfunction "B_2") (pintype "input"))
      (node (ref "U15") (pin "12") (pinfunction "5Y_12") (pintype "output"))
      (node (ref "U16") (pin "3") (pinfunction "DI_3") (pintype "bidirectional"))
      (node (ref "U20") (pin "17") (pinfunction "DIN_17") (pintype "bidirectional"))
    )
    (net (code "27") (name "/RTC3V3") (class "Default")
      (node (ref "U15") (pin "6") (pinfunction "3Y_6") (pintype "output"))
      (node (ref "U20") (pin "1") (pinfunction "CS_1") (pintype "bidirectional"))
    )
    (net (code "28") (name "/RTC5V") (class "Default")
      (node (ref "U12") (pin "A2") (pinfunction "A2_A2") (pintype "bidirectional"))
      (node (ref "U15") (pin "7") (pinfunction "3A_7") (pintype "input"))
    )
    (net (code "29") (name "/SCK") (class "Default")
      (node (ref "SCK5V") (pin "1") (pinfunction "1_1") (pintype "passive"))
      (node (ref "U12") (pin "SCK") (pinfunction "SCK_SCK") (pintype "bidirectional"))
      (node (ref "U15") (pin "9") (pinfunction "4A_9") (pintype "input"))
    )
    (net (code "30") (name "/SCK3V3") (class "Default")
      (node (ref "SCK3V3") (pin "1") (pinfunction "1_1") (pintype "passive"))
      (node (ref "U15") (pin "10") (pinfunction "4Y_10") (pintype "output"))
      (node (ref "U16") (pin "5") (pinfunction "SCK_5") (pintype "bidirectional"))
      (node (ref "U17") (pin "P$14") (pinfunction "SCLK_P$14") (pintype "input"))
      (node (ref "U20") (pin "18") (pinfunction "SCLK_18") (pintype "bidirectional"))
      (node (ref "U20") (pin "20") (pinfunction "SCLK_20") (pintype "bidirectional"))
    )
    (net (code "31") (name "/SCL3V3") (class "Default")
      (node (ref "JP2") (pin "P$3") (pinfunction "3_P$3") (pintype "passive"))
      (node (ref "Q1") (pin "2") (pinfunction "S_2") (pintype "bidirectional"))
      (node (ref "R7") (pin "1") (pinfunction "1_1") (pintype "passive"))
      (node (ref "SCL3V3") (pin "1") (pinfunction "1_1") (pintype "passive"))
      (node (ref "U2") (pin "3") (pinfunction "SCL_3") (pintype "output"))
      (node (ref "U6") (pin "3") (pinfunction "SCL_3") (pintype "output"))
    )
    (net (code "32") (name "/SCL5V") (class "Default")
      (node (ref "Q1") (pin "3") (pinfunction "D_3") (pintype "bidirectional"))
      (node (ref "R9") (pin "1") (pinfunction "1_1") (pintype "passive"))
      (node (ref "SCL5V") (pin "1") (pinfunction "1_1") (pintype "passive"))
      (node (ref "U12") (pin "21") (pinfunction "21(SCL)_21") (pintype "bidirectional"))
      (node (ref "U24") (pin "3") (pinfunction "SCL_3") (pintype "output"))
    )
    (net (code "33") (name "/SDA3V3") (class "Default")
      (node (ref "JP2") (pin "P$4") (pinfunction "4_P$4") (pintype "passive"))
      (node (ref "Q2") (pin "2") (pinfunction "S_2") (pintype "bidirectional"))
      (node (ref "R5") (pin "1") (pinfunction "1_1") (pintype "passive"))
      (node (ref "SDA3V3") (pin "1") (pinfunction "1_1") (pintype "passive"))
      (node (ref "U2") (pin "4") (pinfunction "SDA_4") (pintype "output"))
      (node (ref "U6") (pin "4") (pinfunction "SDA_4") (pintype "output"))
    )
    (net (code "34") (name "/SDA5V") (class "Default")
      (node (ref "Q2") (pin "3") (pinfunction "D_3") (pintype "bidirectional"))
      (node (ref "R11") (pin "1") (pinfunction "1_1") (pintype "passive"))
      (node (ref "SDA5V") (pin "1") (pinfunction "1_1") (pintype "passive"))
      (node (ref "U12") (pin "20") (pinfunction "20(SDA)_20") (pintype "bidirectional"))
      (node (ref "U24") (pin "4") (pinfunction "SDA_4") (pintype "output"))
    )
    (net (code "35") (name "/SDCARD3V3") (class "Default")
      (node (ref "U15") (pin "4") (pinfunction "2Y_4") (pintype "output"))
      (node (ref "U16") (pin "2") (pinfunction "CS_2") (pintype "bidirectional"))
    )
    (net (code "36") (name "/SDCARD5V") (class "Default")
      (node (ref "U12") (pin "A5") (pinfunction "A5_A5") (pintype "bidirectional"))
      (node (ref "U15") (pin "5") (pinfunction "2A_5") (pintype "input"))
    )
    (net (code "37") (name "/SERIAL_COMM_ON") (class "Default")
      (node (ref "U12") (pin "2") (pinfunction "2_2") (pintype "bidirectional"))
      (node (ref "U8") (pin "2") (pinfunction "IN_A_2") (pintype "input"))
    )
    (net (code "38") (name "/SERIAL_COMM_ON_3V3") (class "Default")
      (node (ref "R8") (pin "2") (pinfunction "2_2") (pintype "passive"))
      (node (ref "U26") (pin "8") (pinfunction "OE_8") (pintype "input"))
      (node (ref "U8") (pin "4") (pinfunction "OUT_Y_4") (pintype "output"))
    )
    (net (code "39") (name "/SHTDN") (class "Default")
      (node (ref "R27") (pin "1") (pinfunction "1_1") (pintype "passive"))
      (node (ref "U12") (pin "A0") (pinfunction "A0_A0") (pintype "bidirectional"))
    )
    (net (code "40") (name "/TEMP1") (class "Default")
      (node (ref "U12") (pin "3") (pinfunction "3_3") (pintype "bidirectional"))
      (node (ref "U7") (pin "2") (pinfunction "IN_A_2") (pintype "input"))
    )
    (net (code "41") (name "/TEMP2") (class "Default")
      (node (ref "U11") (pin "1") (pinfunction "IN_1") (pintype "input"))
      (node (ref "U12") (pin "4") (pinfunction "4_4") (pintype "bidirectional"))
    )
    (net (code "42") (name "/UCAM_POWER") (class "Default")
      (node (ref "R30") (pin "1") (pinfunction "1_1") (pintype "passive"))
      (node (ref "U12") (pin "12") (pinfunction "12_12") (pintype "bidirectional"))
    )
    (net (code "43") (name "/UCAM_RESET") (class "Default")
      (node (ref "R32") (pin "1") (pinfunction "1_1") (pintype "passive"))
      (node (ref "U12") (pin "13") (pinfunction "13_13") (pintype "bidirectional"))
    )
    (net (code "44") (name "/UCAM_RXD") (class "Default")
      (node (ref "U12") (pin "17") (pinfunction "17(RX2)_17") (pintype "bidirectional"))
      (node (ref "U26") (pin "13") (pinfunction "B3_13") (pintype "bidirectional"))
    )
    (net (code "45") (name "/UCAM_RX_3V3") (class "Default")
      (node (ref "JP9") (pin "P$3") (pinfunction "3_P$3") (pintype "passive"))
      (node (ref "U26") (pin "5") (pinfunction "A4_5") (pintype "bidirectional"))
    )
    (net (code "46") (name "/UCAM_TXD") (class "Default")
      (node (ref "U12") (pin "16") (pinfunction "16(TX2)_16") (pintype "bidirectional"))
      (node (ref "U26") (pin "12") (pinfunction "B4_12") (pintype "bidirectional"))
    )
    (net (code "47") (name "/UCAM_TX_3V3") (class "Default")
      (node (ref "JP9") (pin "P$2") (pinfunction "2_P$2") (pintype "passive"))
      (node (ref "U26") (pin "4") (pinfunction "A3_4") (pintype "bidirectional"))
    )
    (net (code "48") (name "GND") (class "Default")
      (node (ref "B1") (pin "-") (pinfunction "-_-") (pintype "passive"))
      (node (ref "B2") (pin "-") (pinfunction "-_-") (pintype "passive"))
      (node (ref "C10") (pin "2") (pinfunction "2_2") (pintype "passive"))
      (node (ref "C11") (pin "2") (pinfunction "2_2") (pintype "passive"))
      (node (ref "C12") (pin "2") (pinfunction "2_2") (pintype "passive"))
      (node (ref "C13") (pin "2") (pinfunction "2_2") (pintype "passive"))
      (node (ref "C14") (pin "2") (pinfunction "2_2") (pintype "passive"))
      (node (ref "C15") (pin "2") (pinfunction "2_2") (pintype "passive"))
      (node (ref "C16") (pin "2") (pinfunction "2_2") (pintype "passive"))
      (node (ref "C17") (pin "2") (pinfunction "2_2") (pintype "passive"))
      (node (ref "C18") (pin "2") (pinfunction "2_2") (pintype "passive"))
      (node (ref "C19") (pin "2") (pinfunction "2_2") (pintype "passive"))
      (node (ref "C2") (pin "2") (pinfunction "2_2") (pintype "passive"))
      (node (ref "C20") (pin "2") (pinfunction "2_2") (pintype "passive"))
      (node (ref "C21") (pin "2") (pinfunction "2_2") (pintype "passive"))
      (node (ref "C22") (pin "2") (pinfunction "2_2") (pintype "passive"))
      (node (ref "C23") (pin "2") (pinfunction "2_2") (pintype "passive"))
      (node (ref "C24") (pin "2") (pinfunction "2_2") (pintype "passive"))
      (node (ref "C25") (pin "2") (pinfunction "2_2") (pintype "passive"))
      (node (ref "C26") (pin "2") (pinfunction "2_2") (pintype "passive"))
      (node (ref "C27") (pin "2") (pinfunction "2_2") (pintype "passive"))
      (node (ref "C28") (pin "2") (pinfunction "2_2") (pintype "passive"))
      (node (ref "C29") (pin "2") (pinfunction "2_2") (pintype "passive"))
      (node (ref "C3") (pin "2") (pinfunction "2_2") (pintype "passive"))
      (node (ref "C4") (pin "2") (pinfunction "2_2") (pintype "passive"))
      (node (ref "C5") (pin "1") (pinfunction "1_1") (pintype "passive"))
      (node (ref "C6") (pin "2") (pinfunction "2_2") (pintype "passive"))
      (node (ref "C7") (pin "2") (pinfunction "2_2") (pintype "passive"))
      (node (ref "C8") (pin "2") (pinfunction "2_2") (pintype "passive"))
      (node (ref "C9") (pin "2") (pinfunction "2_2") (pintype "passive"))
      (node (ref "GND1") (pin "1") (pinfunction "1_1") (pintype "passive"))
      (node (ref "GND2") (pin "1") (pinfunction "1_1") (pintype "passive"))
      (node (ref "GND3") (pin "1") (pinfunction "1_1") (pintype "passive"))
      (node (ref "JP1") (pin "P$2") (pinfunction "2_P$2") (pintype "passive"))
      (node (ref "JP2") (pin "P$2") (pinfunction "2_P$2") (pintype "passive"))
      (node (ref "JP3") (pin "P$1") (pinfunction "1_P$1") (pintype "passive"))
      (node (ref "JP4") (pin "P$2") (pinfunction "2_P$2") (pintype "passive"))
      (node (ref "JP5") (pin "2") (pinfunction "GND_2") (pintype "passive"))
      (node (ref "JP5") (pin "3") (pinfunction "GND_3") (pintype "passive"))
      (node (ref "JP5") (pin "4") (pinfunction "GND_4") (pintype "passive"))
      (node (ref "JP5") (pin "5") (pinfunction "GND_5") (pintype "passive"))
      (node (ref "JP6") (pin "P$2") (pinfunction "2_P$2") (pintype "passive"))
      (node (ref "JP7") (pin "P$2") (pinfunction "2_P$2") (pintype "passive"))
      (node (ref "JP8") (pin "1") (pinfunction "1_1") (pintype "passive"))
      (node (ref "JP9") (pin "P$4") (pinfunction "4_P$4") (pintype "passive"))
      (node (ref "R12") (pin "1") (pinfunction "1_1") (pintype "passive"))
      (node (ref "R26") (pin "2") (pinfunction "2_2") (pintype "passive"))
      (node (ref "R3") (pin "1") (pinfunction "1_1") (pintype "passive"))
      (node (ref "U1") (pin "3") (pinfunction "GND_3") (pintype "input"))
      (node (ref "U1") (pin "4") (pinfunction "GNDS_4") (pintype "input"))
      (node (ref "U10") (pin "3") (pinfunction "GND_3") (pintype "passive"))
      (node (ref "U11") (pin "3") (pinfunction "GND_3") (pintype "passive"))
      (node (ref "U12") (pin "GND") (pinfunction "GND_GND") (pintype "bidirectional"))
      (node (ref "U12") (pin "GND.") (pinfunction "GND._GND.") (pintype "bidirectional"))
      (node (ref "U12") (pin "GND..") (pinfunction "GND.._GND..") (pintype "bidirectional"))
      (node (ref "U14") (pin "1") (pinfunction "~{OE}_1") (pintype "input"))
      (node (ref "U14") (pin "3") (pinfunction "GND_3") (pintype "passive"))
      (node (ref "U15") (pin "8") (pinfunction "GND_8") (pintype "passive"))
      (node (ref "U16") (pin "6") (pinfunction "GND_6") (pintype "bidirectional"))
      (node (ref "U17") (pin "P$2") (pinfunction "GND$1_P$2") (pintype "power_in"))
      (node (ref "U17") (pin "P$4") (pinfunction "GND$2_P$4") (pintype "power_in"))
      (node (ref "U17") (pin "P$5") (pinfunction "GND$3_P$5") (pintype "power_in"))
      (node (ref "U18") (pin "2") (pinfunction "GND_2") (pintype "power_in"))
      (node (ref "U19") (pin "3") (pinfunction "GND_3") (pintype "passive"))
      (node (ref "U2") (pin "2") (pinfunction "GND_2") (pintype "passive"))
      (node (ref "U2") (pin "6") (pinfunction "VIN-_6") (pintype "input"))
      (node (ref "U20") (pin "10") (pinfunction "GND_10") (pintype "bidirectional"))
      (node (ref "U20") (pin "11") (pinfunction "GND_11") (pintype "bidirectional"))
      (node (ref "U20") (pin "12") (pinfunction "GND_12") (pintype "bidirectional"))
      (node (ref "U20") (pin "13") (pinfunction "GND_13") (pintype "bidirectional"))
      (node (ref "U20") (pin "14") (pinfunction "GND_14") (pintype "bidirectional"))
      (node (ref "U20") (pin "15") (pinfunction "GND_15") (pintype "bidirectional"))
      (node (ref "U20") (pin "2") (pinfunction "GND_2") (pintype "bidirectional"))
      (node (ref "U20") (pin "7") (pinfunction "GND_7") (pintype "bidirectional"))
      (node (ref "U20") (pin "8") (pinfunction "GND_8") (pintype "bidirectional"))
      (node (ref "U20") (pin "9") (pinfunction "GND_9") (pintype "bidirectional"))
      (node (ref "U21") (pin "3") (pinfunction "GND_3") (pintype "power_in"))
      (node (ref "U22") (pin "2") (pinfunction "V-_2") (pintype "power_in"))
      (node (ref "U24") (pin "2") (pinfunction "GND_2") (pintype "passive"))
      (node (ref "U25") (pin "4") (pinfunction "GND_4") (pintype "passive"))
      (node (ref "U26") (pin "9") (pinfunction "GND_9") (pintype "passive"))
      (node (ref "U3") (pin "2") (pinfunction "V-_2") (pintype "passive"))
      (node (ref "U4") (pin "3") (pinfunction "GND_3") (pintype "input"))
      (node (ref "U4") (pin "4") (pinfunction "GNDS_4") (pintype "input"))
      (node (ref "U5") (pin "3") (pinfunction "GND_3") (pintype "bidirectional"))
      (node (ref "U6") (pin "2") (pinfunction "GND_2") (pintype "passive"))
      (node (ref "U6") (pin "6") (pinfunction "VIN-_6") (pintype "input"))
      (node (ref "U7") (pin "3") (pinfunction "GND_3") (pintype "passive"))
      (node (ref "U8") (pin "3") (pinfunction "GND_3") (pintype "passive"))
      (node (ref "U9") (pin "P$12") (pinfunction "GND_P$12") (pintype "bidirectional"))
      (node (ref "U9") (pin "P$19") (pinfunction "GND_P$19") (pintype "bidirectional"))
      (node (ref "U9") (pin "P$3") (pinfunction "GND_P$3") (pintype "bidirectional"))
      (node (ref "U9") (pin "P$8") (pinfunction "GND_P$8") (pintype "bidirectional"))
    )
    (net (code "49") (name "Net-(B1-+)") (class "Default")
      (node (ref "B1") (pin "+$1") (pinfunction "+_+$1") (pintype "passive"))
      (node (ref "B1") (pin "+$2") (pinfunction "+1_+$2") (pintype "passive"))
      (node (ref "U9") (pin "P$4") (pinfunction "VBACKUP_P$4") (pintype "bidirectional"))
    )
    (net (code "50") (name "Net-(B2-+)") (class "Default")
      (node (ref "B2") (pin "+$1") (pinfunction "+_+$1") (pintype "passive"))
      (node (ref "B2") (pin "+$2") (pinfunction "+1_+$2") (pintype "passive"))
      (node (ref "U20") (pin "16") (pinfunction "VBAT_16") (pintype "bidirectional"))
    )
    (net (code "51") (name "Net-(D1-C)") (class "Default")
      (node (ref "C13") (pin "1") (pinfunction "1_1") (pintype "passive"))
      (node (ref "D1") (pin "1") (pinfunction "C_1") (pintype "passive"))
      (node (ref "U12") (pin "5V") (pinfunction "5V_5V") (pintype "bidirectional"))
    )
    (net (code "52") (name "Net-(D3-PadA)") (class "Default")
      (node (ref "D3") (pin "A") (pinfunction "A_A") (pintype "passive"))
      (node (ref "R27") (pin "2") (pinfunction "2_2") (pintype "passive"))
    )
    (net (code "53") (name "Net-(JP1-1)") (class "Default")
      (node (ref "C1") (pin "1") (pinfunction "1_1") (pintype "passive"))
      (node (ref "JP1") (pin "P$1") (pinfunction "1_P$1") (pintype "passive"))
      (node (ref "R1") (pin "1") (pinfunction "1_1") (pintype "passive"))
      (node (ref "U3") (pin "4") (pinfunction "-IN_4") (pintype "input"))
    )
    (net (code "54") (name "Net-(JP3-2)") (class "Default")
      (node (ref "JP3") (pin "P$2") (pinfunction "2_P$2") (pintype "passive"))
      (node (ref "U11") (pin "6") (pinfunction "NO_6") (pintype "passive"))
    )
    (net (code "55") (name "Net-(JP4-1)") (class "Default")
      (node (ref "JP4") (pin "P$1") (pinfunction "1_P$1") (pintype "passive"))
      (node (ref "U11") (pin "4") (pinfunction "NC_4") (pintype "passive"))
    )
    (net (code "56") (name "Net-(JP5-SIG)") (class "Default")
      (node (ref "JP5") (pin "1") (pinfunction "SIG_1") (pintype "passive"))
      (node (ref "U9") (pin "P$11") (pinfunction "EX_ANT_P$11") (pintype "bidirectional"))
    )
    (net (code "57") (name "Net-(JP6-1)") (class "Default")
      (node (ref "C18") (pin "1") (pinfunction "1_1") (pintype "passive"))
      (node (ref "JP6") (pin "P$1") (pinfunction "1_P$1") (pintype "passive"))
      (node (ref "R29") (pin "1") (pinfunction "1_1") (pintype "passive"))
      (node (ref "U21") (pin "5") (pinfunction "IN_5") (pintype "input"))
      (node (ref "VBATT") (pin "1") (pinfunction "1_1") (pintype "passive"))
    )
    (net (code "58") (name "Net-(JP7-1)") (class "Default")
      (node (ref "JP7") (pin "P$1") (pinfunction "1_P$1") (pintype "passive"))
      (node (ref "Q7") (pin "3") (pinfunction "C_3") (pintype "passive"))
    )
    (net (code "59") (name "Net-(JP7-3)") (class "Default")
      (node (ref "JP7") (pin "P$3") (pinfunction "3_P$3") (pintype "passive"))
      (node (ref "U24") (pin "1") (pinfunction "VIN+_1") (pintype "input"))
    )
    (net (code "60") (name "Net-(JP7-4)") (class "Default")
      (node (ref "JP7") (pin "P$4") (pinfunction "4_P$4") (pintype "passive"))
      (node (ref "U24") (pin "6") (pinfunction "VIN-_6") (pintype "input"))
      (node (ref "U25") (pin "1") (pinfunction "NO1_1") (pintype "passive"))
      (node (ref "U25") (pin "5") (pinfunction "NO2_5") (pintype "passive"))
    )
    (net (code "61") (name "Net-(JP7-5)") (class "Default")
      (node (ref "JP7") (pin "P$5") (pinfunction "5_P$5") (pintype "passive"))
      (node (ref "U25") (pin "2") (pinfunction "COM1_2") (pintype "passive"))
    )
    (net (code "62") (name "Net-(JP7-6)") (class "Default")
      (node (ref "JP7") (pin "P$6") (pinfunction "6_P$6") (pintype "passive"))
      (node (ref "U25") (pin "6") (pinfunction "COM2_6") (pintype "passive"))
    )
    (net (code "63") (name "Net-(JP8-Pad4)") (class "Default")
      (node (ref "JP8") (pin "4") (pinfunction "4_4") (pintype "passive"))
      (node (ref "R25") (pin "2") (pinfunction "2_2") (pintype "passive"))
    )
    (net (code "64") (name "Net-(JP9-1)") (class "Default")
      (node (ref "JP9") (pin "P$1") (pinfunction "1_P$1") (pintype "passive"))
      (node (ref "Q8") (pin "3") (pinfunction "C_3") (pintype "passive"))
    )
    (net (code "65") (name "Net-(JP9-5)") (class "Default")
      (node (ref "JP9") (pin "P$5") (pinfunction "5_P$5") (pintype "passive"))
      (node (ref "R32") (pin "2") (pinfunction "2_2") (pintype "passive"))
    )
    (net (code "66") (name "Net-(Q3-B)") (class "Default")
      (node (ref "Q3") (pin "1") (pinfunction "B_1") (pintype "passive"))
      (node (ref "R23") (pin "2") (pinfunction "2_2") (pintype "passive"))
      (node (ref "R24") (pin "1") (pinfunction "1_1") (pintype "passive"))
    )
    (net (code "67") (name "Net-(Q3-C)") (class "Default")
      (node (ref "JP8") (pin "3") (pinfunction "3_3") (pintype "passive"))
      (node (ref "Q3") (pin "3") (pinfunction "C_3") (pintype "passive"))
    )
    (net (code "68") (name "Net-(Q4-B)") (class "Default")
      (node (ref "Q4") (pin "1") (pinfunction "B_1") (pintype "passive"))
      (node (ref "R18") (pin "2") (pinfunction "2_2") (pintype "passive"))
      (node (ref "R20") (pin "1") (pinfunction "1_1") (pintype "passive"))
    )
    (net (code "69") (name "Net-(Q5-B)") (class "Default")
      (node (ref "Q5") (pin "1") (pinfunction "B_1") (pintype "passive"))
      (node (ref "R17") (pin "2") (pinfunction "2_2") (pintype "passive"))
      (node (ref "R19") (pin "1") (pinfunction "1_1") (pintype "passive"))
    )
    (net (code "70") (name "Net-(Q6-B)") (class "Default")
      (node (ref "Q6") (pin "1") (pinfunction "B_1") (pintype "passive"))
      (node (ref "R21") (pin "2") (pinfunction "2_2") (pintype "passive"))
      (node (ref "R22") (pin "1") (pinfunction "1_1") (pintype "passive"))
    )
    (net (code "71") (name "Net-(Q6-C)") (class "Default")
      (node (ref "C11") (pin "1") (pinfunction "1_1") (pintype "passive"))
      (node (ref "Q6") (pin "3") (pinfunction "C_3") (pintype "passive"))
      (node (ref "U9") (pin "P$1") (pinfunction "VCC_P$1") (pintype "bidirectional"))
    )
    (net (code "72") (name "Net-(Q7-B)") (class "Default")
      (node (ref "Q7") (pin "1") (pinfunction "B_1") (pintype "passive"))
      (node (ref "R15") (pin "2") (pinfunction "2_2") (pintype "passive"))
      (node (ref "R16") (pin "1") (pinfunction "1_1") (pintype "passive"))
    )
    (net (code "73") (name "Net-(Q8-B)") (class "Default")
      (node (ref "Q8") (pin "1") (pinfunction "B_1") (pintype "passive"))
      (node (ref "R30") (pin "2") (pinfunction "2_2") (pintype "passive"))
      (node (ref "R31") (pin "1") (pinfunction "1_1") (pintype "passive"))
    )
    (net (code "74") (name "Net-(U1-NR)") (class "Default")
      (node (ref "C3") (pin "1") (pinfunction "1_1") (pintype "passive"))
      (node (ref "U1") (pin "1") (pinfunction "NR_1") (pintype "bidirectional"))
    )
    (net (code "75") (name "Net-(U1-OUTF)") (class "Default")
      (node (ref "+3VP*") (pin "1") (pinfunction "1_1") (pintype "passive"))
      (node (ref "C4") (pin "1") (pinfunction "1_1") (pintype "passive"))
      (node (ref "C5") (pin "2") (pinfunction "2_2") (pintype "passive"))
      (node (ref "R2") (pin "2") (pinfunction "2_2") (pintype "passive"))
      (node (ref "U1") (pin "6") (pinfunction "OUTS_6") (pintype "output"))
      (node (ref "U1") (pin "7") (pinfunction "OUTF_7") (pintype "output"))
      (node (ref "U2") (pin "5") (pinfunction "VDD_5") (pintype "power_in"))
      (node (ref "U3") (pin "5") (pinfunction "V+_5") (pintype "power_in"))
    )
    (net (code "76") (name "Net-(U2-VIN+)") (class "Default")
      (node (ref "C1") (pin "2") (pinfunction "2_2") (pintype "passive"))
      (node (ref "R1") (pin "2") (pinfunction "2_2") (pintype "passive"))
      (node (ref "U2") (pin "1") (pinfunction "VIN+_1") (pintype "input"))
      (node (ref "U3") (pin "1") (pinfunction "OUT_1") (pintype "output"))
      (node (ref "VPAR") (pin "1") (pinfunction "1_1") (pintype "passive"))
    )
    (net (code "77") (name "Net-(U3-+IN)") (class "Default")
      (node (ref "C2") (pin "1") (pinfunction "1_1") (pintype "passive"))
      (node (ref "R2") (pin "1") (pinfunction "1_1") (pintype "passive"))
      (node (ref "R3") (pin "2") (pinfunction "2_2") (pintype "passive"))
      (node (ref "U3") (pin "3") (pinfunction "+IN_3") (pintype "input"))
    )
    (net (code "78") (name "Net-(U4-NR)") (class "Default")
      (node (ref "C7") (pin "1") (pinfunction "1_1") (pintype "passive"))
      (node (ref "U4") (pin "1") (pinfunction "NR_1") (pintype "bidirectional"))
    )
    (net (code "79") (name "Net-(U4-OUTF)") (class "Default")
      (node (ref "+3VT*") (pin "1") (pinfunction "1_1") (pintype "passive"))
      (node (ref "C8") (pin "1") (pinfunction "1_1") (pintype "passive"))
      (node (ref "U4") (pin "6") (pinfunction "OUTS_6") (pintype "output"))
      (node (ref "U4") (pin "7") (pinfunction "OUTF_7") (pintype "output"))
      (node (ref "U6") (pin "5") (pinfunction "VDD_5") (pintype "power_in"))
    )
    (net (code "80") (name "Net-(U5-IN1)") (class "Default")
      (node (ref "R10") (pin "2") (pinfunction "2_2") (pintype "passive"))
      (node (ref "U5") (pin "1") (pinfunction "IN1_1") (pintype "bidirectional"))
      (node (ref "U5") (pin "5") (pinfunction "IN2_5") (pintype "bidirectional"))
      (node (ref "U7") (pin "4") (pinfunction "OUT_Y_4") (pintype "output"))
    )
    (net (code "81") (name "Net-(U5-S1B)") (class "Default")
      (node (ref "R12") (pin "2") (pinfunction "2_2") (pintype "passive"))
      (node (ref "U5") (pin "7") (pinfunction "S2B_7") (pintype "bidirectional"))
      (node (ref "U5") (pin "9") (pinfunction "S1B_9") (pintype "bidirectional"))
    )
    (net (code "82") (name "Net-(U10-Y)") (class "Default")
      (node (ref "U10") (pin "4") (pinfunction "Y_4") (pintype "output"))
      (node (ref "U17") (pin "P$13") (pinfunction "MOSI_P$13") (pintype "input"))
    )
    (net (code "83") (name "Net-(U11-COM)") (class "Default")
      (node (ref "U11") (pin "5") (pinfunction "COM_5") (pintype "output"))
      (node (ref "U5") (pin "2") (pinfunction "S1A_2") (pintype "bidirectional"))
      (node (ref "U5") (pin "4") (pinfunction "S2A_4") (pintype "bidirectional"))
    )
    (net (code "84") (name "Net-(U19-A)") (class "Default")
      (node (ref "R28") (pin "2") (pinfunction "2_2") (pintype "passive"))
      (node (ref "U19") (pin "2") (pinfunction "A_2") (pintype "input"))
      (node (ref "U20") (pin "5") (pinfunction "INT/SQW_5") (pintype "bidirectional"))
    )
    (net (code "85") (name "Net-(U19-VCC)") (class "Default")
      (node (ref "ALARM") (pin "1") (pinfunction "1_1") (pintype "passive"))
      (node (ref "R28") (pin "1") (pinfunction "1_1") (pintype "passive"))
      (node (ref "R29") (pin "2") (pinfunction "2_2") (pintype "passive"))
      (node (ref "U19") (pin "5") (pinfunction "VCC_5") (pintype "power_in"))
    )
    (net (code "86") (name "Net-(U19-Y)") (class "Default")
      (node (ref "D2") (pin "A") (pinfunction "A_A") (pintype "passive"))
      (node (ref "U19") (pin "4") (pinfunction "Y_4") (pintype "output"))
    )
    (net (code "87") (name "Net-(U21-~{SHDN})") (class "Default")
      (node (ref "C22") (pin "1") (pinfunction "1_1") (pintype "passive"))
      (node (ref "D2") (pin "C") (pinfunction "C_C") (pintype "passive"))
      (node (ref "D3") (pin "C") (pinfunction "C_C") (pintype "passive"))
      (node (ref "R26") (pin "1") (pinfunction "1_1") (pintype "passive"))
      (node (ref "SHTDN") (pin "1") (pinfunction "1_1") (pintype "passive"))
      (node (ref "U21") (pin "4") (pinfunction "~{SHDN}_4") (pintype "input"))
    )
    (net (code "88") (name "Net-(U22-+INA)") (class "Default")
      (node (ref "R6") (pin "1") (pinfunction "1_1") (pintype "passive"))
      (node (ref "U22") (pin "1") (pinfunction "+INA_1") (pintype "input"))
      (node (ref "U5") (pin "10") (pinfunction "D1_10") (pintype "bidirectional"))
    )
    (net (code "89") (name "Net-(U22-+INB)") (class "Default")
      (node (ref "C27") (pin "1") (pinfunction "1_1") (pintype "passive"))
      (node (ref "U22") (pin "3") (pinfunction "+INB_3") (pintype "input"))
      (node (ref "U5") (pin "6") (pinfunction "D2_6") (pintype "bidirectional"))
    )
    (net (code "90") (name "Net-(U22--INA)") (class "Default")
      (node (ref "U22") (pin "7") (pinfunction "OUTA_7") (pintype "output"))
      (node (ref "U22") (pin "8") (pinfunction "-INA_8") (pintype "input"))
      (node (ref "U23") (pin "4") (pinfunction "GND_4") (pintype "passive"))
    )
    (net (code "91") (name "Net-(U22--INB)") (class "Default")
      (node (ref "U22") (pin "4") (pinfunction "-INB_4") (pintype "input"))
      (node (ref "U22") (pin "5") (pinfunction "OUTB_5") (pintype "output"))
      (node (ref "U6") (pin "1") (pinfunction "VIN+_1") (pintype "input"))
    )
    (net (code "92") (name "Net-(U23-VOUT)") (class "Default")
      (node (ref "R4") (pin "1") (pinfunction "1_1") (pintype "passive"))
      (node (ref "R6") (pin "2") (pinfunction "2_2") (pintype "passive"))
      (node (ref "U23") (pin "6") (pinfunction "VOUT_6") (pintype "passive"))
    )
    (net (code "93") (name "Net-(U25-IN1)") (class "Default")
      (node (ref "R13") (pin "2") (pinfunction "2_2") (pintype "passive"))
      (node (ref "U25") (pin "7") (pinfunction "IN1_7") (pintype "input"))
    )
    (net (code "94") (name "Net-(U25-IN2)") (class "Default")
      (node (ref "R14") (pin "2") (pinfunction "2_2") (pintype "passive"))
      (node (ref "U25") (pin "3") (pinfunction "IN2_3") (pintype "input"))
    )
    (net (code "95") (name "unconnected-(JP8-Pad2)") (class "Default")
      (node (ref "JP8") (pin "2") (pinfunction "2_2") (pintype "passive"))
    )
    (net (code "96") (name "unconnected-(JP8-Pad6)") (class "Default")
      (node (ref "JP8") (pin "6") (pinfunction "6_6") (pintype "passive"))
    )
    (net (code "97") (name "unconnected-(JP8-Pad7)") (class "Default")
      (node (ref "JP8") (pin "7") (pinfunction "7_7") (pintype "passive"))
    )
    (net (code "98") (name "unconnected-(JP8-Pad8)") (class "Default")
      (node (ref "JP8") (pin "8") (pinfunction "8_8") (pintype "passive"))
    )
    (net (code "99") (name "unconnected-(JP8-Pad9)") (class "Default")
      (node (ref "JP8") (pin "9") (pinfunction "9_9") (pintype "passive"))
    )
    (net (code "100") (name "unconnected-(U7-NC-Pad1)") (class "Default")
      (node (ref "U7") (pin "1") (pinfunction "NC_1") (pintype "no_connect"))
    )
    (net (code "101") (name "unconnected-(U8-NC-Pad1)") (class "Default")
      (node (ref "U8") (pin "1") (pinfunction "NC_1") (pintype "no_connect"))
    )
    (net (code "102") (name "unconnected-(U9-1PPS-PadP$13)") (class "Default")
      (node (ref "U9") (pin "P$13") (pinfunction "1PPS_P$13") (pintype "bidirectional"))
    )
    (net (code "103") (name "unconnected-(U9-3D-FIX-PadP$5)") (class "Default")
      (node (ref "U9") (pin "P$5") (pinfunction "3D-FIX_P$5") (pintype "bidirectional"))
    )
    (net (code "104") (name "unconnected-(U9-NC-PadP$6)") (class "Default")
      (node (ref "U9") (pin "P$6") (pinfunction "NC_P$6") (pintype "bidirectional"))
    )
    (net (code "105") (name "unconnected-(U9-NC-PadP$7)") (class "Default")
      (node (ref "U9") (pin "P$7") (pinfunction "NC_P$7") (pintype "bidirectional"))
    )
    (net (code "106") (name "unconnected-(U9-NC-PadP$15)") (class "Default")
      (node (ref "U9") (pin "P$15") (pinfunction "NC_P$15") (pintype "bidirectional"))
    )
    (net (code "107") (name "unconnected-(U9-NC-PadP$16)") (class "Default")
      (node (ref "U9") (pin "P$16") (pinfunction "NC_P$16") (pintype "bidirectional"))
    )
    (net (code "108") (name "unconnected-(U9-NC-PadP$17)") (class "Default")
      (node (ref "U9") (pin "P$17") (pinfunction "NC_P$17") (pintype "bidirectional"))
    )
    (net (code "109") (name "unconnected-(U9-NC-PadP$18)") (class "Default")
      (node (ref "U9") (pin "P$18") (pinfunction "NC_P$18") (pintype "bidirectional"))
    )
    (net (code "110") (name "unconnected-(U9-NC-PadP$20)") (class "Default")
      (node (ref "U9") (pin "P$20") (pinfunction "NC_P$20") (pintype "bidirectional"))
    )
    (net (code "111") (name "unconnected-(U9-NRESET-PadP$2)") (class "Default")
      (node (ref "U9") (pin "P$2") (pinfunction "NRESET_P$2") (pintype "bidirectional"))
    )
    (net (code "112") (name "unconnected-(U9-RTCM-PadP$14)") (class "Default")
      (node (ref "U9") (pin "P$14") (pinfunction "RTCM_P$14") (pintype "bidirectional"))
    )
    (net (code "113") (name "unconnected-(U12-(N{slash}C)-PadN{slash}C)") (class "Default")
      (node (ref "U12") (pin "N/C") (pinfunction "(N/C)_N/C") (pintype "bidirectional"))
    )
    (net (code "114") (name "unconnected-(U12-+5V.-Pad5V.)") (class "Default")
      (node (ref "U12") (pin "5V.") (pinfunction "+5V._5V.") (pintype "bidirectional"))
    )
    (net (code "115") (name "unconnected-(U12-+5V..-Pad5V..)") (class "Default")
      (node (ref "U12") (pin "5V..") (pinfunction "+5V.._5V..") (pintype "bidirectional"))
    )
    (net (code "116") (name "unconnected-(U12-0(RX)-Pad0)") (class "Default")
      (node (ref "U12") (pin "0") (pinfunction "0(RX)_0") (pintype "bidirectional"))
    )
    (net (code "117") (name "unconnected-(U12-1(TX)-Pad1)") (class "Default")
      (node (ref "U12") (pin "1") (pinfunction "1(TX)_1") (pintype "bidirectional"))
    )
    (net (code "118") (name "unconnected-(U12-IOREF-PadI{slash}OREF)") (class "Default")
      (node (ref "U12") (pin "I/OREF") (pinfunction "IOREF_I/OREF") (pintype "bidirectional"))
    )
    (net (code "119") (name "unconnected-(U12-Pad+5V_)") (class "Default")
      (node (ref "U12") (pin "+5V_") (pinfunction "+5V__+5V_") (pintype "bidirectional"))
    )
    (net (code "120") (name "unconnected-(U12-Pad3.3V)") (class "Default")
      (node (ref "U12") (pin "3.3V") (pinfunction "3.3V_3.3V") (pintype "bidirectional"))
    )
    (net (code "121") (name "unconnected-(U12-Pad5)") (class "Default")
      (node (ref "U12") (pin "5") (pinfunction "5_5") (pintype "bidirectional"))
    )
    (net (code "122") (name "unconnected-(U12-Pad7)") (class "Default")
      (node (ref "U12") (pin "7") (pinfunction "7_7") (pintype "bidirectional"))
    )
    (net (code "123") (name "unconnected-(U12-Pad10)") (class "Default")
      (node (ref "U12") (pin "10") (pinfunction "10_10") (pintype "bidirectional"))
    )
    (net (code "124") (name "unconnected-(U12-Pad22)") (class "Default")
      (node (ref "U12") (pin "22") (pinfunction "22_22") (pintype "bidirectional"))
    )
    (net (code "125") (name "unconnected-(U12-Pad23)") (class "Default")
      (node (ref "U12") (pin "23") (pinfunction "23_23") (pintype "bidirectional"))
    )
    (net (code "126") (name "unconnected-(U12-Pad25)") (class "Default")
      (node (ref "U12") (pin "25") (pinfunction "25_25") (pintype "bidirectional"))
    )
    (net (code "127") (name "unconnected-(U12-Pad27)") (class "Default")
      (node (ref "U12") (pin "27") (pinfunction "27_27") (pintype "bidirectional"))
    )
    (net (code "128") (name "unconnected-(U12-Pad29)") (class "Default")
      (node (ref "U12") (pin "29") (pinfunction "29_29") (pintype "bidirectional"))
    )
    (net (code "129") (name "unconnected-(U12-Pad30)") (class "Default")
      (node (ref "U12") (pin "30") (pinfunction "30_30") (pintype "bidirectional"))
    )
    (net (code "130") (name "unconnected-(U12-Pad31)") (class "Default")
      (node (ref "U12") (pin "31") (pinfunction "31_31") (pintype "bidirectional"))
    )
    (net (code "131") (name "unconnected-(U12-Pad33)") (class "Default")
      (node (ref "U12") (pin "33") (pinfunction "33_33") (pintype "bidirectional"))
    )
    (net (code "132") (name "unconnected-(U12-Pad34)") (class "Default")
      (node (ref "U12") (pin "34") (pinfunction "34_34") (pintype "bidirectional"))
    )
    (net (code "133") (name "unconnected-(U12-Pad35)") (class "Default")
      (node (ref "U12") (pin "35") (pinfunction "35_35") (pintype "bidirectional"))
    )
    (net (code "134") (name "unconnected-(U12-Pad36)") (class "Default")
      (node (ref "U12") (pin "36") (pinfunction "36_36") (pintype "bidirectional"))
    )
    (net (code "135") (name "unconnected-(U12-Pad37)") (class "Default")
      (node (ref "U12") (pin "37") (pinfunction "37_37") (pintype "bidirectional"))
    )
    (net (code "136") (name "unconnected-(U12-Pad38)") (class "Default")
      (node (ref "U12") (pin "38") (pinfunction "38_38") (pintype "bidirectional"))
    )
    (net (code "137") (name "unconnected-(U12-Pad39)") (class "Default")
      (node (ref "U12") (pin "39") (pinfunction "39_39") (pintype "bidirectional"))
    )
    (net (code "138") (name "unconnected-(U12-Pad40)") (class "Default")
      (node (ref "U12") (pin "40") (pinfunction "40_40") (pintype "bidirectional"))
    )
    (net (code "139") (name "unconnected-(U12-Pad41)") (class "Default")
      (node (ref "U12") (pin "41") (pinfunction "41_41") (pintype "bidirectional"))
    )
    (net (code "140") (name "unconnected-(U12-Pad42)") (class "Default")
      (node (ref "U12") (pin "42") (pinfunction "42_42") (pintype "bidirectional"))
    )
    (net (code "141") (name "unconnected-(U12-Pad43)") (class "Default")
      (node (ref "U12") (pin "43") (pinfunction "43_43") (pintype "bidirectional"))
    )
    (net (code "142") (name "unconnected-(U12-Pad44)") (class "Default")
      (node (ref "U12") (pin "44") (pinfunction "44_44") (pintype "bidirectional"))
    )
    (net (code "143") (name "unconnected-(U12-Pad45)") (class "Default")
      (node (ref "U12") (pin "45") (pinfunction "45_45") (pintype "bidirectional"))
    )
    (net (code "144") (name "unconnected-(U12-Pad46)") (class "Default")
      (node (ref "U12") (pin "46") (pinfunction "46_46") (pintype "bidirectional"))
    )
    (net (code "145") (name "unconnected-(U12-Pad47)") (class "Default")
      (node (ref "U12") (pin "47") (pinfunction "47_47") (pintype "bidirectional"))
    )
    (net (code "146") (name "unconnected-(U12-Pad48)") (class "Default")
      (node (ref "U12") (pin "48") (pinfunction "48_48") (pintype "bidirectional"))
    )
    (net (code "147") (name "unconnected-(U12-Pad49)") (class "Default")
      (node (ref "U12") (pin "49") (pinfunction "49_49") (pintype "bidirectional"))
    )
    (net (code "148") (name "unconnected-(U12-Pad50)") (class "Default")
      (node (ref "U12") (pin "50") (pinfunction "50_50") (pintype "bidirectional"))
    )
    (net (code "149") (name "unconnected-(U12-Pad51)") (class "Default")
      (node (ref "U12") (pin "51") (pinfunction "51_51") (pintype "bidirectional"))
    )
    (net (code "150") (name "unconnected-(U12-Pad52)") (class "Default")
      (node (ref "U12") (pin "52") (pinfunction "52_52") (pintype "bidirectional"))
    )
    (net (code "151") (name "unconnected-(U12-Pad53)") (class "Default")
      (node (ref "U12") (pin "53") (pinfunction "53_53") (pintype "bidirectional"))
    )
    (net (code "152") (name "unconnected-(U12-PadA1)") (class "Default")
      (node (ref "U12") (pin "A1") (pinfunction "A1_A1") (pintype "bidirectional"))
    )
    (net (code "153") (name "unconnected-(U12-PadA3)") (class "Default")
      (node (ref "U12") (pin "A3") (pinfunction "A3_A3") (pintype "bidirectional"))
    )
    (net (code "154") (name "unconnected-(U12-PadA4)") (class "Default")
      (node (ref "U12") (pin "A4") (pinfunction "A4_A4") (pintype "bidirectional"))
    )
    (net (code "155") (name "unconnected-(U12-PadA6)") (class "Default")
      (node (ref "U12") (pin "A6") (pinfunction "A6_A6") (pintype "bidirectional"))
    )
    (net (code "156") (name "unconnected-(U12-PadA7)") (class "Default")
      (node (ref "U12") (pin "A7") (pinfunction "A7_A7") (pintype "bidirectional"))
    )
    (net (code "157") (name "unconnected-(U12-PadA9)") (class "Default")
      (node (ref "U12") (pin "A9") (pinfunction "A9_A9") (pintype "bidirectional"))
    )
    (net (code "158") (name "unconnected-(U12-PadA10)") (class "Default")
      (node (ref "U12") (pin "A10") (pinfunction "A10_A10") (pintype "bidirectional"))
    )
    (net (code "159") (name "unconnected-(U12-PadA11)") (class "Default")
      (node (ref "U12") (pin "A11") (pinfunction "A11_A11") (pintype "bidirectional"))
    )
    (net (code "160") (name "unconnected-(U12-PadA12)") (class "Default")
      (node (ref "U12") (pin "A12") (pinfunction "A12_A12") (pintype "bidirectional"))
    )
    (net (code "161") (name "unconnected-(U12-PadA13)") (class "Default")
      (node (ref "U12") (pin "A13") (pinfunction "A13_A13") (pintype "bidirectional"))
    )
    (net (code "162") (name "unconnected-(U12-PadA14)") (class "Default")
      (node (ref "U12") (pin "A14") (pinfunction "A14_A14") (pintype "bidirectional"))
    )
    (net (code "163") (name "unconnected-(U12-PadA15)") (class "Default")
      (node (ref "U12") (pin "A15") (pinfunction "A15_A15") (pintype "bidirectional"))
    )
    (net (code "164") (name "unconnected-(U12-PadAREF)") (class "Default")
      (node (ref "U12") (pin "AREF") (pinfunction "AREF_AREF") (pintype "bidirectional"))
    )
    (net (code "165") (name "unconnected-(U12-PadGND...)") (class "Default")
      (node (ref "U12") (pin "GND...") (pinfunction "GND..._GND...") (pintype "bidirectional"))
    )
    (net (code "166") (name "unconnected-(U12-PadGND....)") (class "Default")
      (node (ref "U12") (pin "GND....") (pinfunction "GND...._GND....") (pintype "bidirectional"))
    )
    (net (code "167") (name "unconnected-(U12-PadGND__)") (class "Default")
      (node (ref "U12") (pin "GND__") (pinfunction "GND___GND__") (pintype "bidirectional"))
    )
    (net (code "168") (name "unconnected-(U12-PadRESET)") (class "Default")
      (node (ref "U12") (pin "RESET") (pinfunction "RESET_RESET") (pintype "bidirectional"))
    )
    (net (code "169") (name "unconnected-(U12-PadRESET.)") (class "Default")
      (node (ref "U12") (pin "RESET.") (pinfunction "RESET._RESET.") (pintype "bidirectional"))
    )
    (net (code "170") (name "unconnected-(U12-PadSCL1)") (class "Default")
      (node (ref "U12") (pin "SCL1") (pinfunction "SCL1_SCL1") (pintype "bidirectional"))
    )
    (net (code "171") (name "unconnected-(U12-PadSDA1)") (class "Default")
      (node (ref "U12") (pin "SDA1") (pinfunction "SDA1_SDA1") (pintype "bidirectional"))
    )
    (net (code "172") (name "unconnected-(U12-PadVIN)") (class "Default")
      (node (ref "U12") (pin "VIN") (pinfunction "VIN_VIN") (pintype "bidirectional"))
    )
    (net (code "173") (name "unconnected-(U15-6A-Pad14)") (class "Default")
      (node (ref "U15") (pin "14") (pinfunction "6A_14") (pintype "input"))
    )
    (net (code "174") (name "unconnected-(U15-6Y-Pad15)") (class "Default")
      (node (ref "U15") (pin "15") (pinfunction "6Y_15") (pintype "output"))
    )
    (net (code "175") (name "unconnected-(U15-NC-Pad16)") (class "Default")
      (node (ref "U15") (pin "16") (pinfunction "NC_16") (pintype "no_connect"))
    )
    (net (code "176") (name "unconnected-(U15-NC_2-Pad13)") (class "Default")
      (node (ref "U15") (pin "13") (pinfunction "NC_2_13") (pintype "no_connect"))
    )
    (net (code "177") (name "unconnected-(U16-NC-Pad1)") (class "Default")
      (node (ref "U16") (pin "1") (pinfunction "NC_1") (pintype "bidirectional"))
    )
    (net (code "178") (name "unconnected-(U16-PadCD1)") (class "Default")
      (node (ref "U16") (pin "CD1") (pinfunction "CD1_CD1") (pintype "bidirectional"))
    )
    (net (code "179") (name "unconnected-(U16-PadCD2)") (class "Default")
      (node (ref "U16") (pin "CD2") (pinfunction "CD2_CD2") (pintype "bidirectional"))
    )
    (net (code "180") (name "unconnected-(U16-RSV-Pad8)") (class "Default")
      (node (ref "U16") (pin "8") (pinfunction "RSV_8") (pintype "bidirectional"))
    )
    (net (code "181") (name "unconnected-(U16-SHIELD-PadGND1)") (class "Default")
      (node (ref "U16") (pin "GND1") (pinfunction "SHIELD_GND1") (pintype "bidirectional"))
    )
    (net (code "182") (name "unconnected-(U16-SHIELD-PadGND3)") (class "Default")
      (node (ref "U16") (pin "GND3") (pinfunction "SHIELD_GND3") (pintype "bidirectional"))
    )
    (net (code "183") (name "unconnected-(U17-INT1-PadP$8)") (class "Default")
      (node (ref "U17") (pin "P$8") (pinfunction "INT1_P$8") (pintype "output"))
    )
    (net (code "184") (name "unconnected-(U17-INT2-PadP$9)") (class "Default")
      (node (ref "U17") (pin "P$9") (pinfunction "INT2_P$9") (pintype "output"))
    )
    (net (code "185") (name "unconnected-(U17-NC-PadP$10)") (class "Default")
      (node (ref "U17") (pin "P$10") (pinfunction "NC_P$10") (pintype "bidirectional"))
    )
    (net (code "186") (name "unconnected-(U17-RESERVED$1-PadP$3)") (class "Default")
      (node (ref "U17") (pin "P$3") (pinfunction "RESERVED$1_P$3") (pintype "bidirectional"))
    )
    (net (code "187") (name "unconnected-(U17-RESERVED$2-PadP$11)") (class "Default")
      (node (ref "U17") (pin "P$11") (pinfunction "RESERVED$2_P$11") (pintype "bidirectional"))
    )
    (net (code "188") (name "unconnected-(U18-NC{slash}FB-Pad4)") (class "Default")
      (node (ref "U18") (pin "4") (pinfunction "NC/FB_4") (pintype "passive"))
    )
    (net (code "189") (name "unconnected-(U19-NC-Pad1)") (class "Default")
      (node (ref "U19") (pin "1") (pinfunction "NC_1") (pintype "no_connect"))
    )
    (net (code "190") (name "unconnected-(U20-32KHZ-Pad3)") (class "Default")
      (node (ref "U20") (pin "3") (pinfunction "32KHZ_3") (pintype "bidirectional"))
    )
    (net (code "191") (name "unconnected-(U20-RST-Pad6)") (class "Default")
      (node (ref "U20") (pin "6") (pinfunction "RST_6") (pintype "bidirectional"))
    )
  )
)
